# Arm_Board.net
KiCad netlist of a schematic drawn in EAGLE
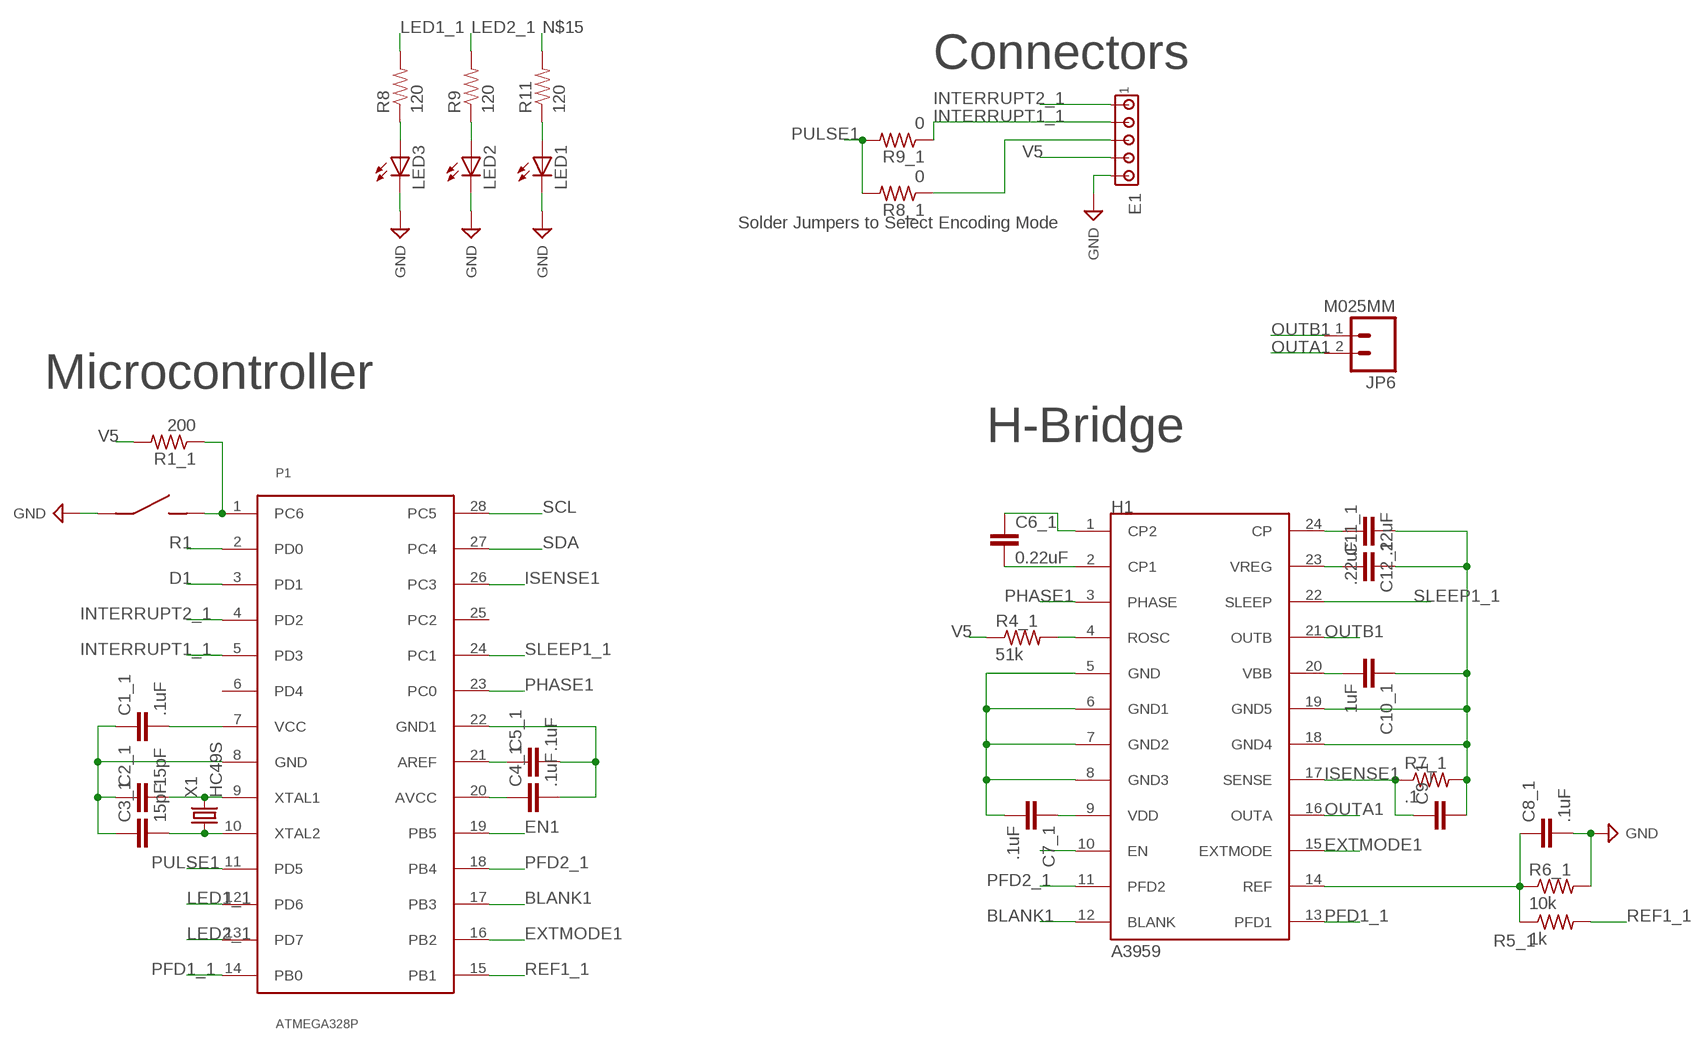
[diagram p0: schematic, sheet 1]
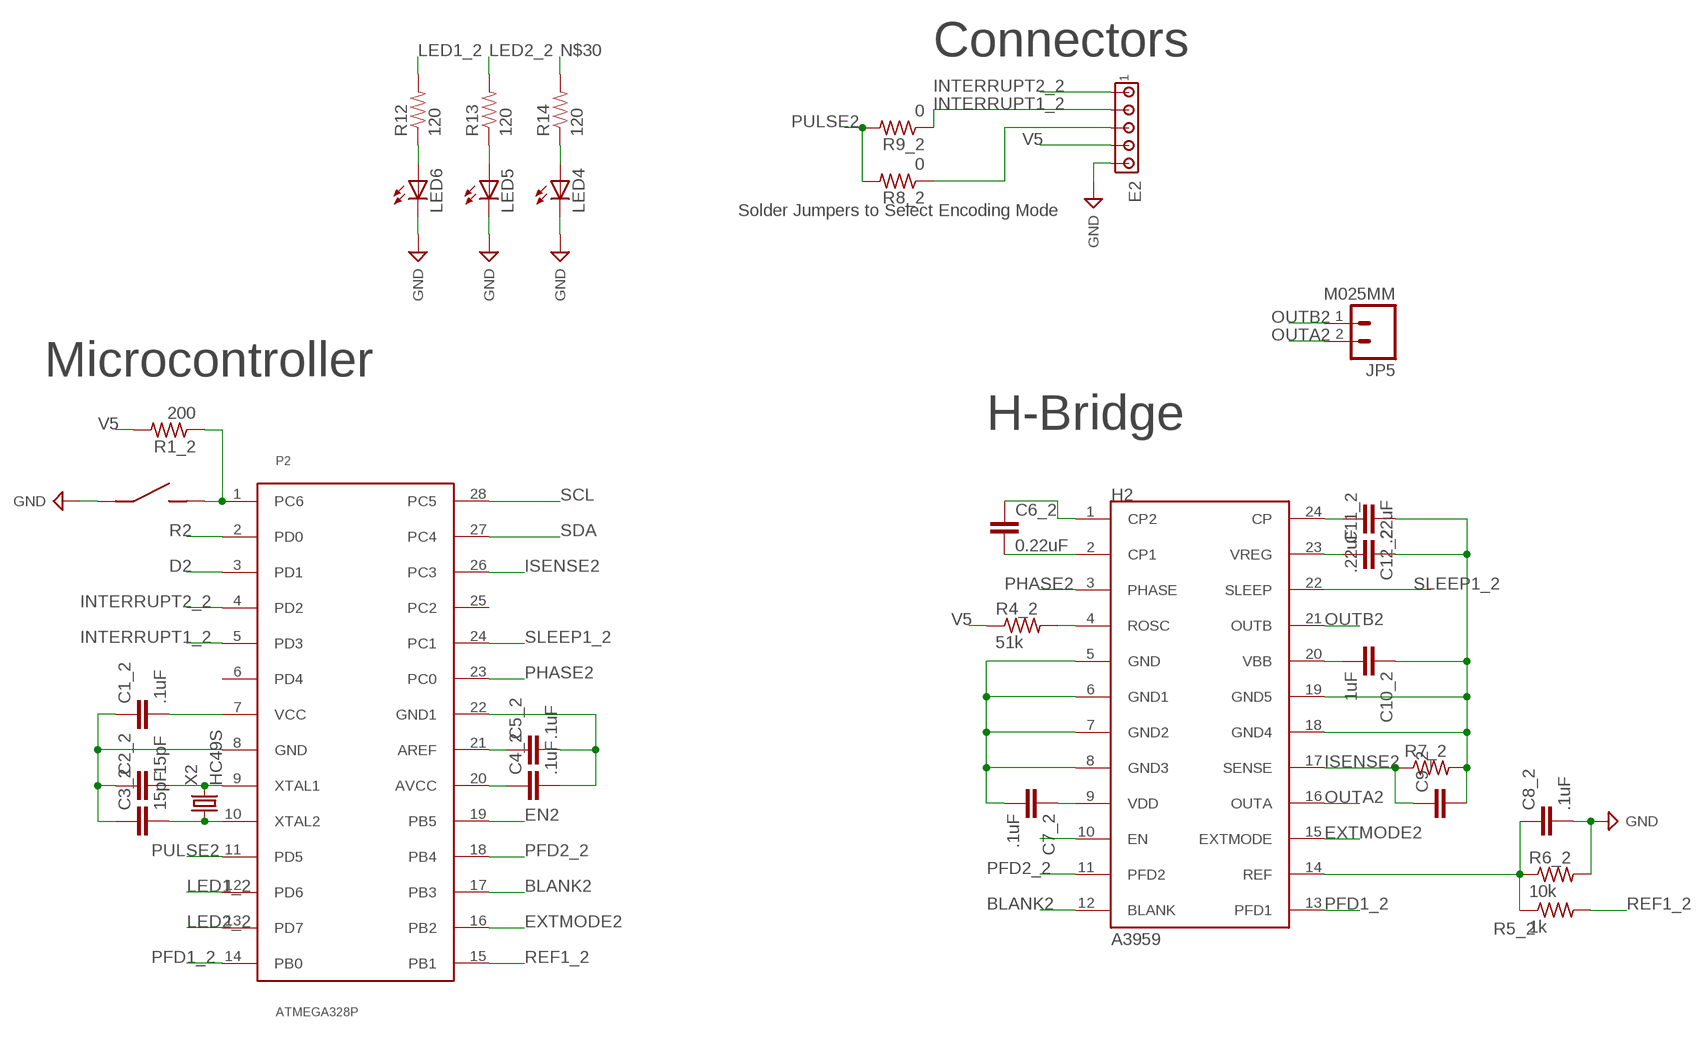
[diagram p1: schematic, sheet 2]
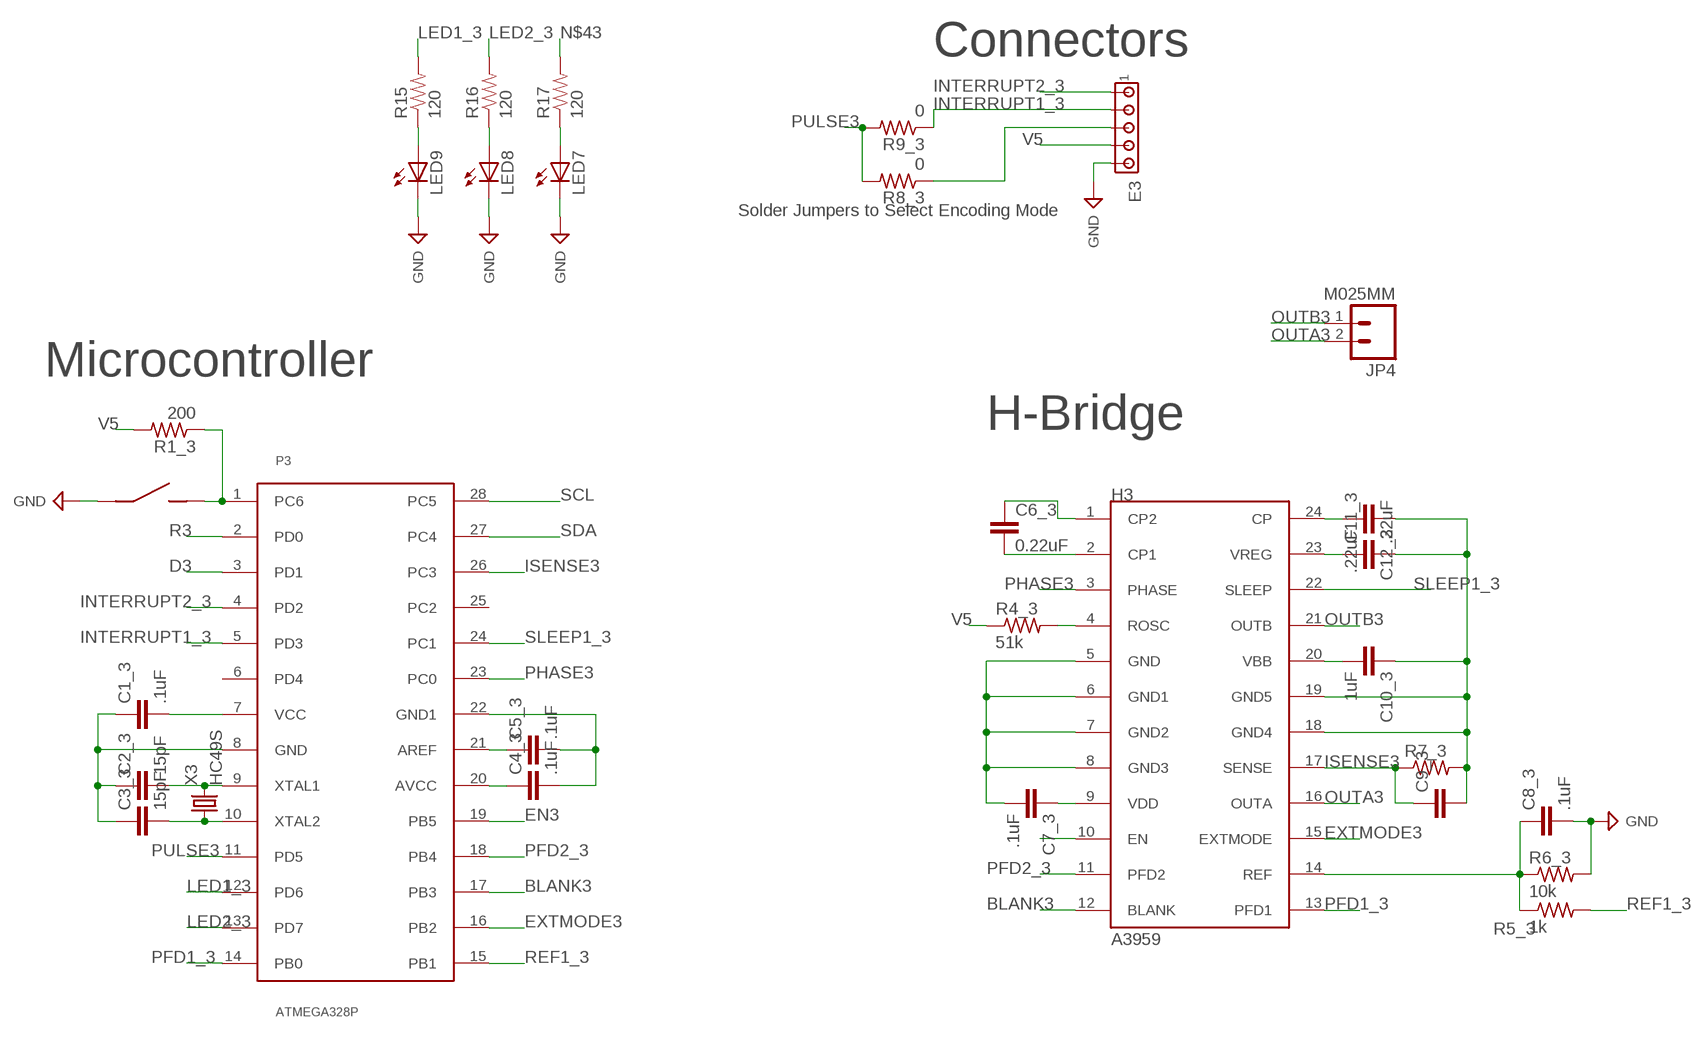
[diagram p2: schematic, sheet 3]
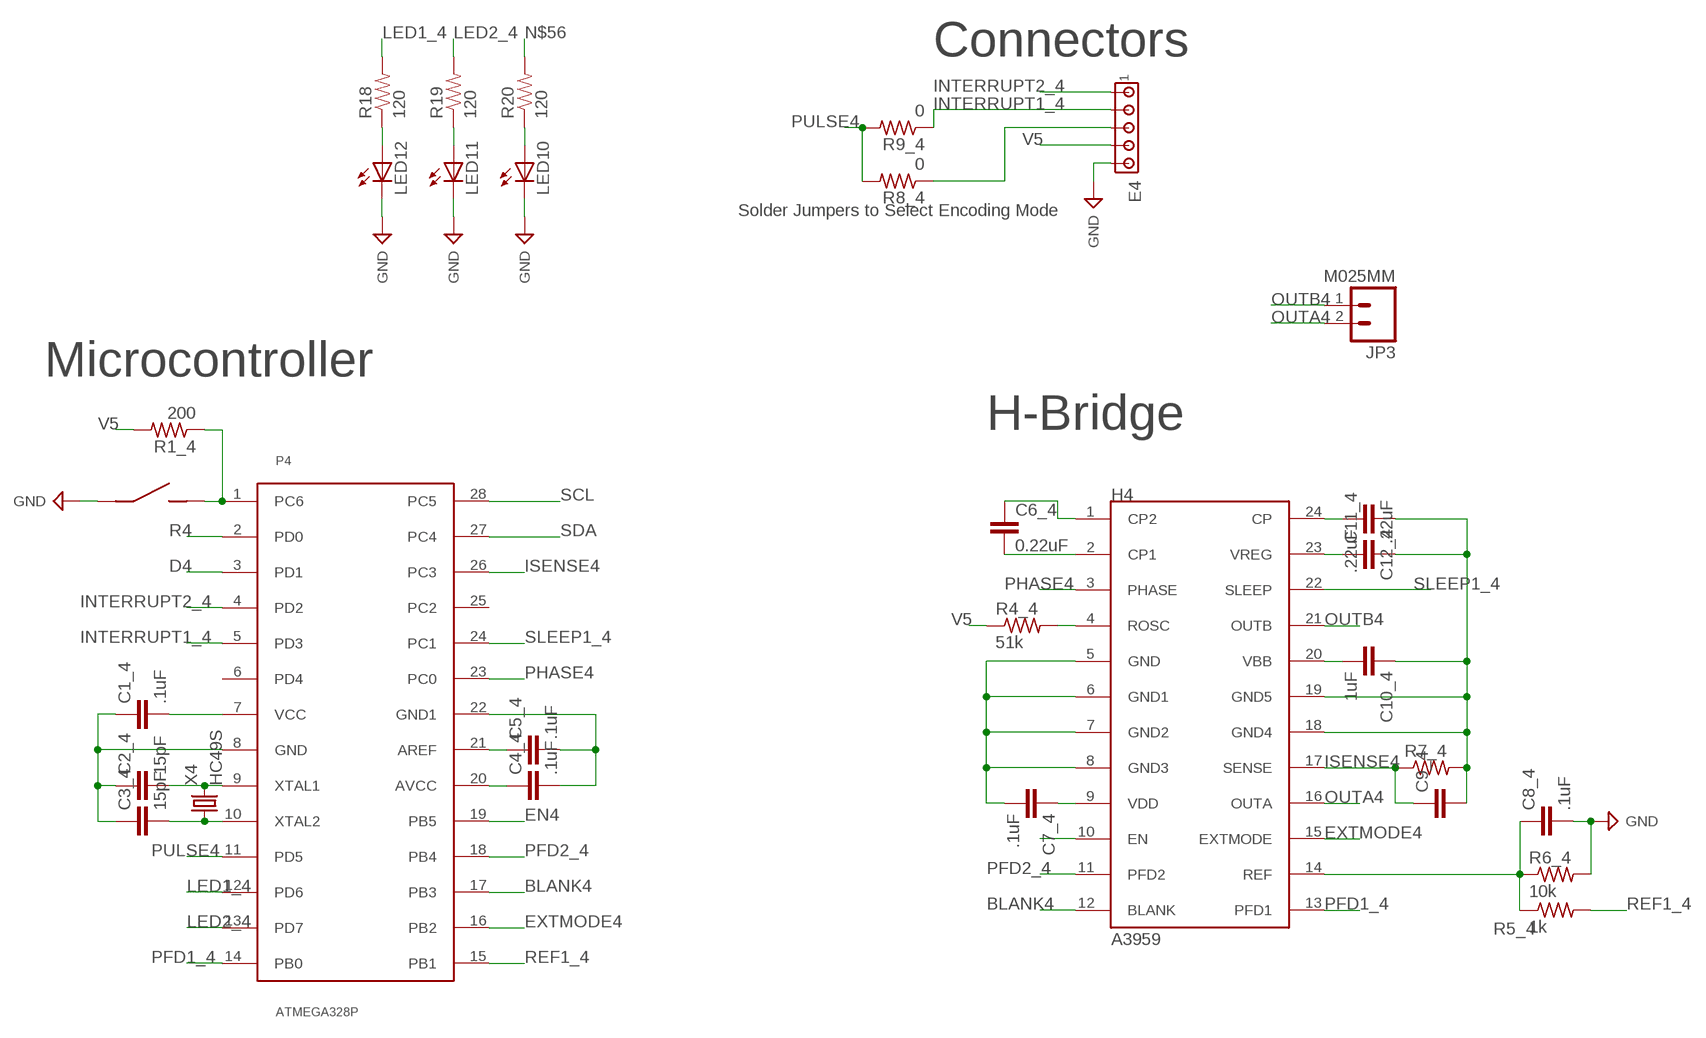
[diagram p3: schematic, sheet 4]
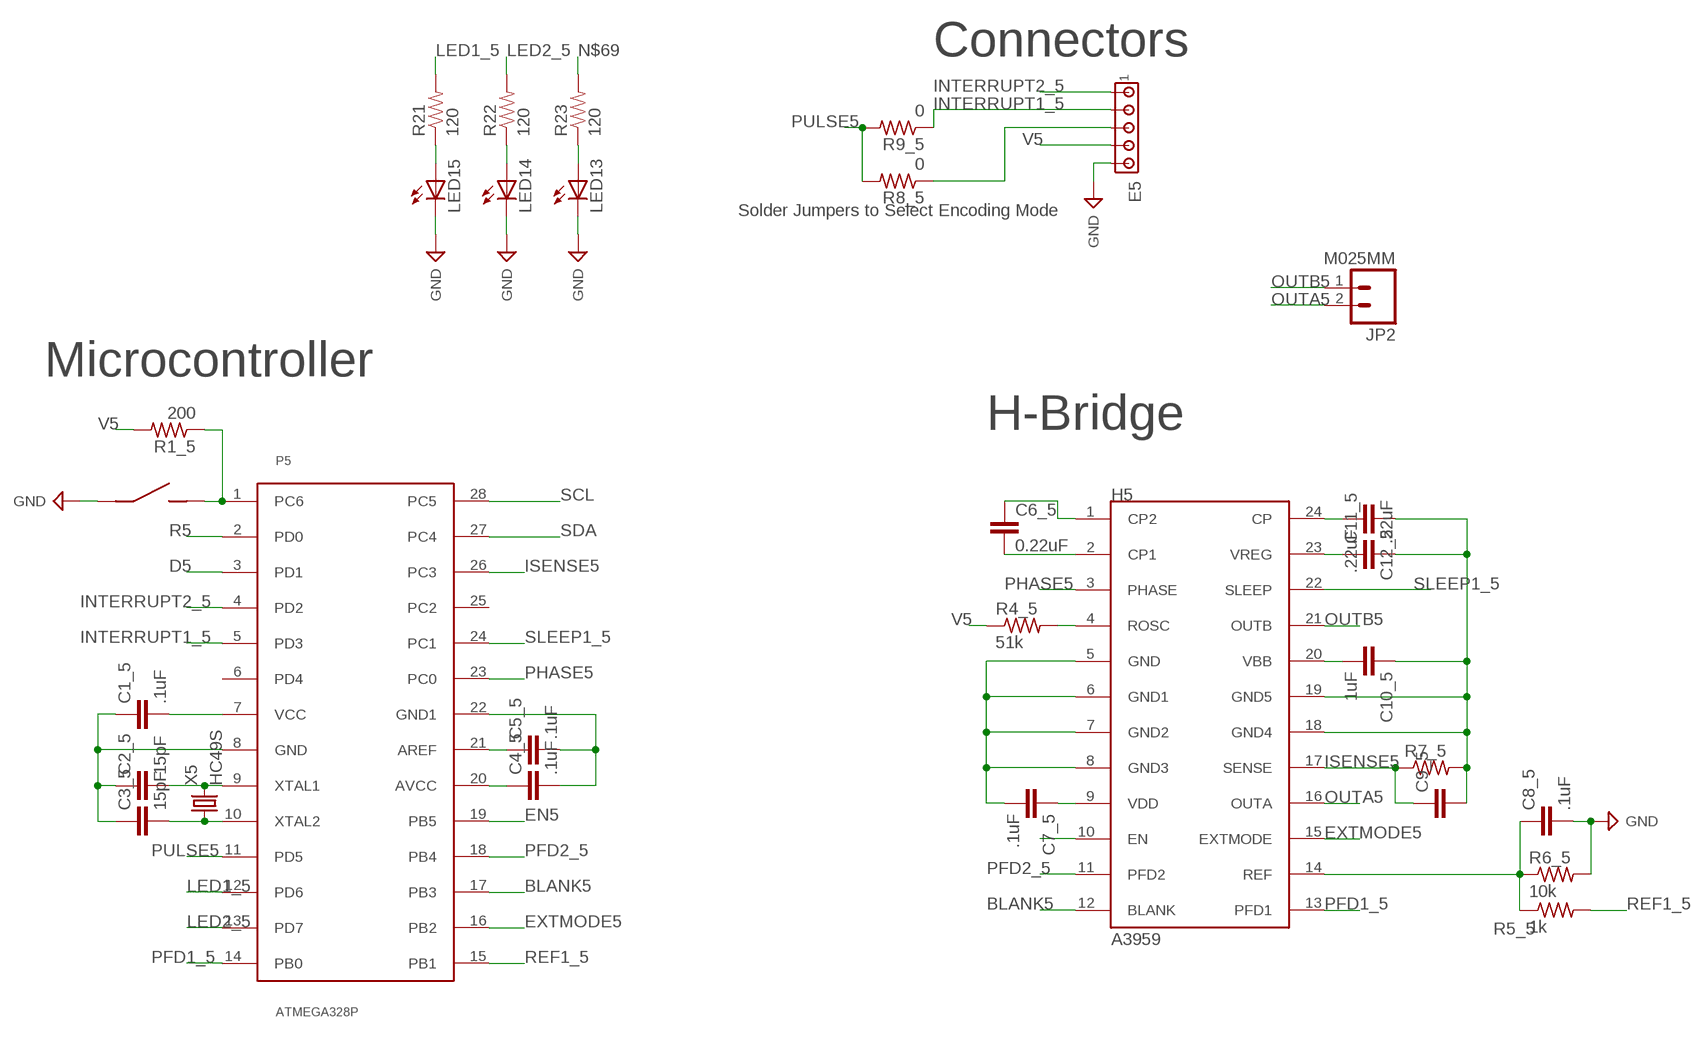
[diagram p4: schematic, sheet 5]
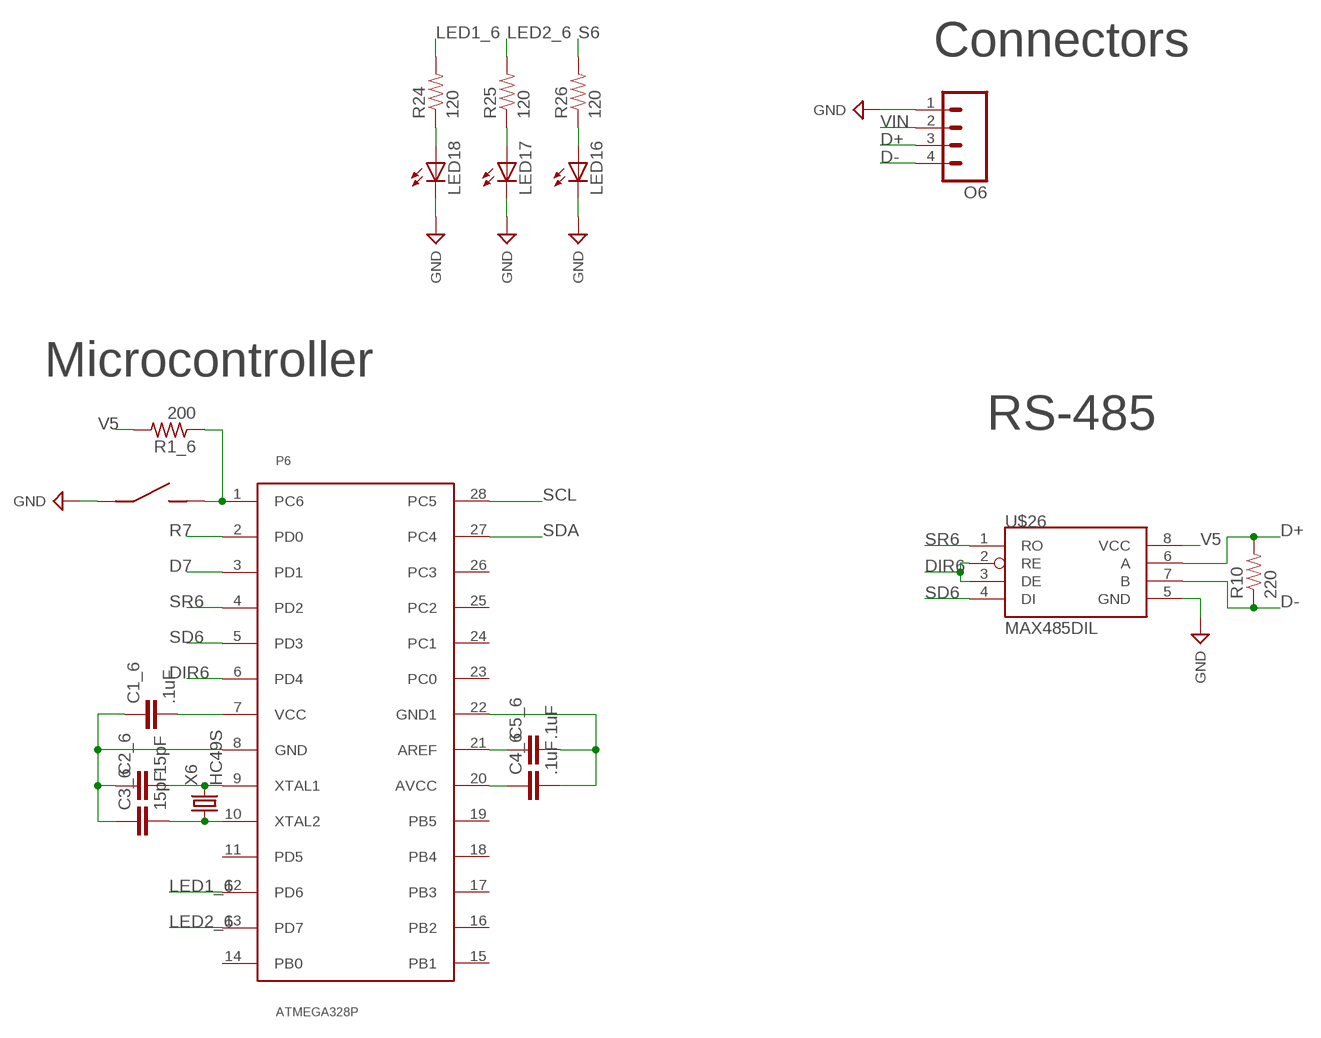
[diagram p5: schematic, sheet 6]
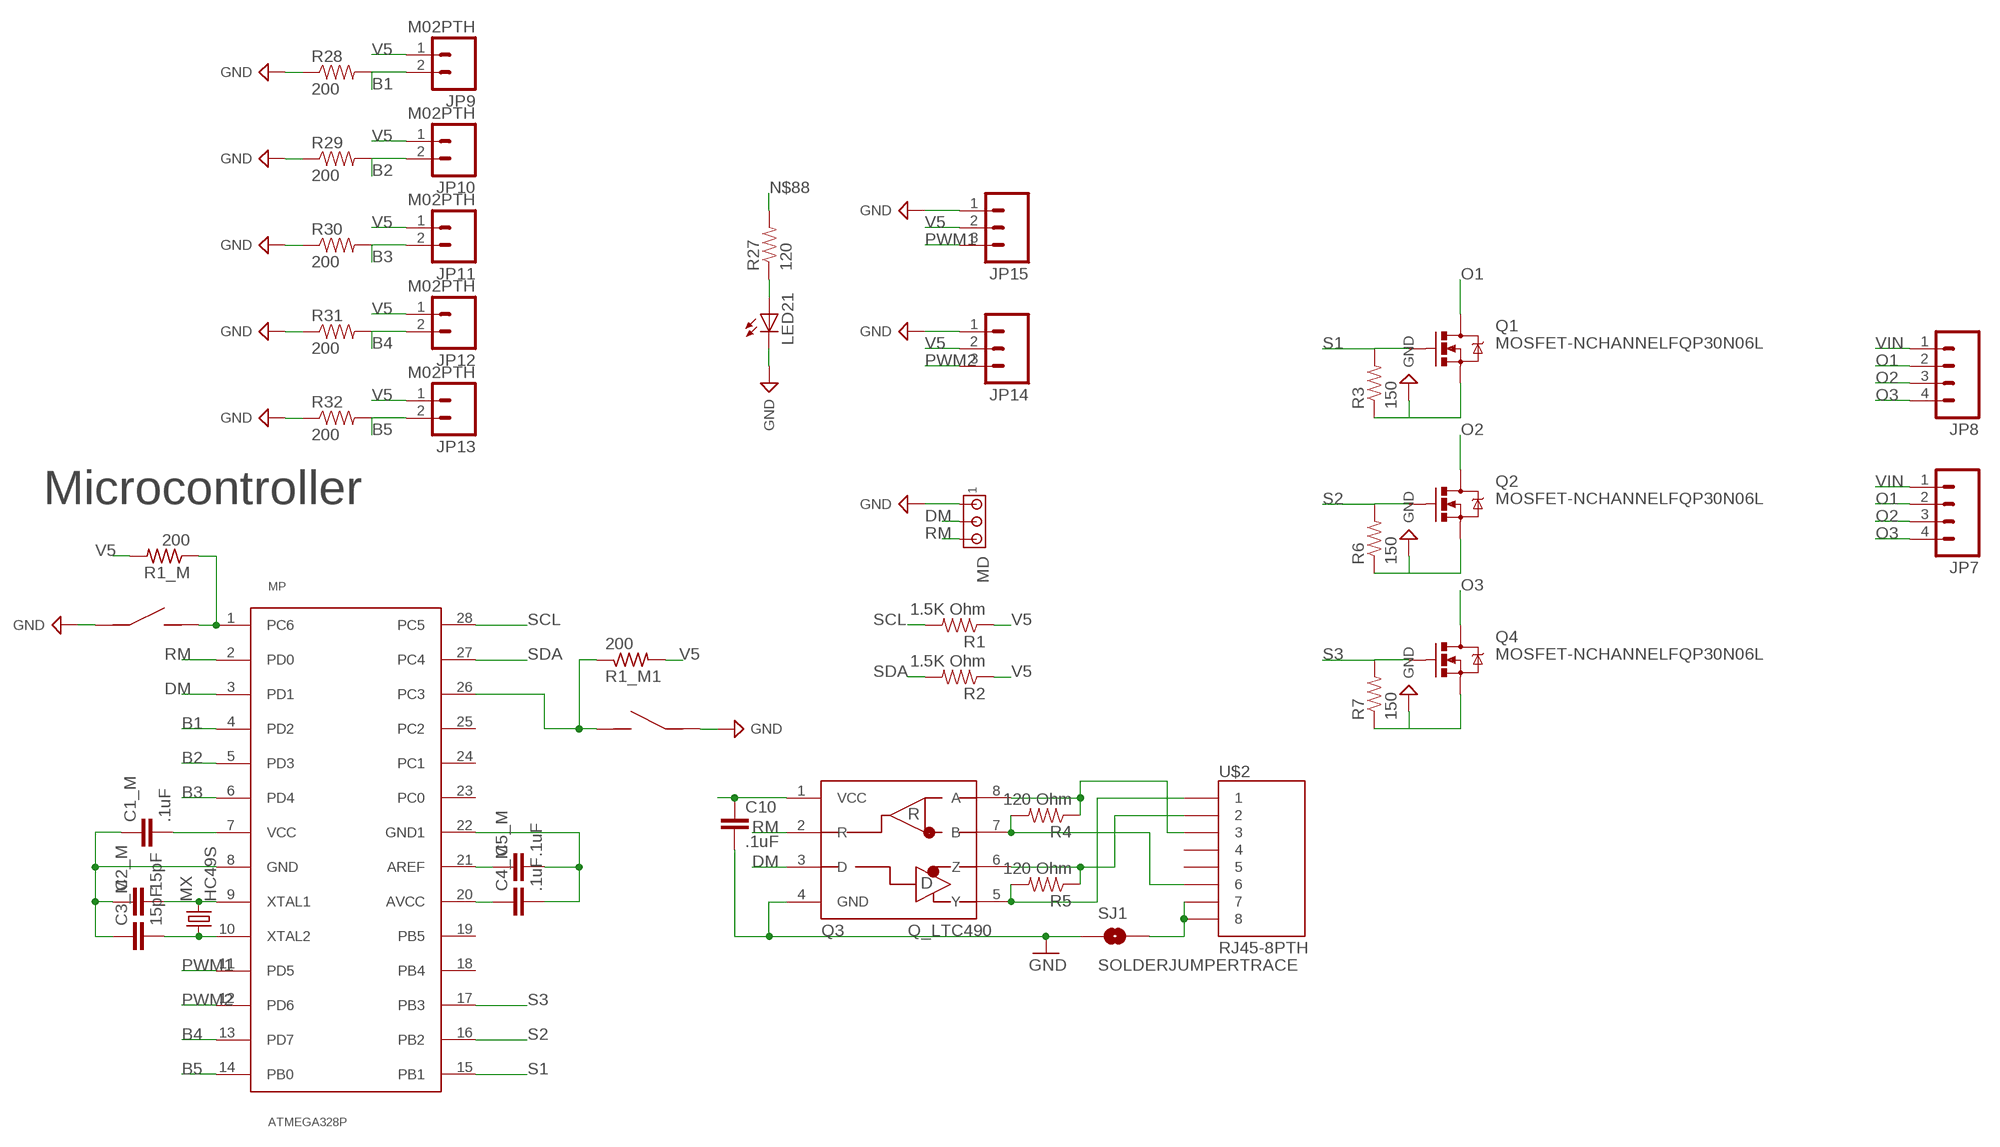
[diagram p6: schematic, sheet 7]
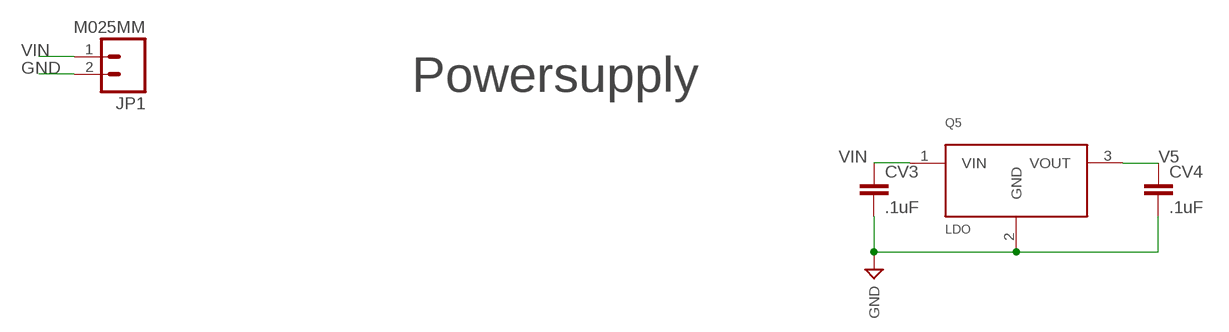
[diagram p7: schematic, sheet 8]

(export (version "E")
  (design (tool "Eeschema 10.0.6"))
  (components
    (comp (ref "CV3")
      (value ".1uF")
      (footprint "eagle-import:C_0805")
      (libsource (lib "eagle-import") (part "C_CAP_0805"))
    )
    (comp (ref "CV4")
      (value ".1uF")
      (footprint "eagle-import:C_0805")
      (libsource (lib "eagle-import") (part "C_CAP_0805"))
    )
    (comp (ref "JP1")
      (value "M025MM")
      (footprint "eagle-import:SCREWTERMINAL-5MM-2")
      (libsource (lib "eagle-import") (part "M025MM"))
    )
    (comp (ref "Q5")
      (value "LDO")
      (footprint "eagle-import:TO-220")
      (libsource (lib "eagle-import") (part "Q_LDO"))
    )
    (comp (ref "C1_6")
      (value ".1uF")
      (footprint "eagle-import:C_0805")
      (libsource (lib "eagle-import") (part "C_CAP_0805"))
    )
    (comp (ref "C2_6")
      (value "15pF")
      (footprint "eagle-import:C_0805")
      (libsource (lib "eagle-import") (part "C_CAP_0805"))
    )
    (comp (ref "C3_6")
      (value "15pF")
      (footprint "eagle-import:C_0805")
      (libsource (lib "eagle-import") (part "C_CAP_0805"))
    )
    (comp (ref "C4_6")
      (value ".1uF")
      (footprint "eagle-import:C_0805")
      (libsource (lib "eagle-import") (part "C_CAP_0805"))
    )
    (comp (ref "C5_6")
      (value ".1uF")
      (footprint "eagle-import:C_0805")
      (libsource (lib "eagle-import") (part "C_CAP_0805"))
    )
    (comp (ref "J6")
      (value "J_MC32857")
      (footprint "eagle-import:J_TOGGLE")
      (libsource (lib "eagle-import") (part "J_MC32857"))
    )
    (comp (ref "LED16")
      (value "LED1206")
      (footprint "eagle-import:LED-1206")
      (libsource (lib "eagle-import") (part "LED1206"))
    )
    (comp (ref "LED17")
      (value "LED1206")
      (footprint "eagle-import:LED-1206")
      (libsource (lib "eagle-import") (part "LED1206"))
    )
    (comp (ref "LED18")
      (value "LED1206")
      (footprint "eagle-import:LED-1206")
      (libsource (lib "eagle-import") (part "LED1206"))
    )
    (comp (ref "O6")
      (value "M041X04_NO_SILK")
      (footprint "eagle-import:1X04_NO_SILK")
      (libsource (lib "eagle-import") (part "M041X04_NO_SILK"))
    )
    (comp (ref "P6")
      (value "ATMEGA328P")
      (footprint "eagle-import:DIP28")
      (libsource (lib "eagle-import") (part "Q_ATMEGA328P"))
    )
    (comp (ref "R1_6")
      (value "200")
      (footprint "eagle-import:R_0805")
      (libsource (lib "eagle-import") (part "R_RES_0805"))
    )
    (comp (ref "R10")
      (value "220")
      (footprint "eagle-import:AXIAL-0.3EZ")
      (libsource (lib "eagle-import") (part "RESISTOREZ"))
    )
    (comp (ref "R24")
      (value "120")
      (footprint "eagle-import:1206")
      (libsource (lib "eagle-import") (part "RESISTOR1206"))
    )
    (comp (ref "R25")
      (value "120")
      (footprint "eagle-import:1206")
      (libsource (lib "eagle-import") (part "RESISTOR1206"))
    )
    (comp (ref "R26")
      (value "120")
      (footprint "eagle-import:1206")
      (libsource (lib "eagle-import") (part "RESISTOR1206"))
    )
    (comp (ref "U$26")
      (value "MAX485DIL")
      (footprint "eagle-import:DIL08")
      (libsource (lib "eagle-import") (part "MAX485DIL"))
    )
    (comp (ref "X6")
      (value "HC49S")
      (footprint "eagle-import:HC-49")
      (libsource (lib "eagle-import") (part "X_HC49SCRYSTAL"))
    )
    (comp (ref "C1_5")
      (value ".1uF")
      (footprint "eagle-import:C_0805")
      (libsource (lib "eagle-import") (part "C_CAP_0805"))
    )
    (comp (ref "C2_5")
      (value "15pF")
      (footprint "eagle-import:C_0805")
      (libsource (lib "eagle-import") (part "C_CAP_0805"))
    )
    (comp (ref "C3_5")
      (value "15pF")
      (footprint "eagle-import:C_0805")
      (libsource (lib "eagle-import") (part "C_CAP_0805"))
    )
    (comp (ref "C4_5")
      (value ".1uF")
      (footprint "eagle-import:C_0805")
      (libsource (lib "eagle-import") (part "C_CAP_0805"))
    )
    (comp (ref "C5_5")
      (value ".1uF")
      (footprint "eagle-import:C_0805")
      (libsource (lib "eagle-import") (part "C_CAP_0805"))
    )
    (comp (ref "C6_5")
      (value "0.22uF")
      (footprint "eagle-import:C_0805")
      (libsource (lib "eagle-import") (part "C_CAP_0805"))
    )
    (comp (ref "C7_5")
      (value ".1uF")
      (footprint "eagle-import:C_0805")
      (libsource (lib "eagle-import") (part "C_CAP_0805"))
    )
    (comp (ref "C8_5")
      (value ".1uF")
      (footprint "eagle-import:C_0805")
      (libsource (lib "eagle-import") (part "C_CAP_0805"))
    )
    (comp (ref "C9_5")
      (value "C_CAP_0805")
      (footprint "eagle-import:C_0805")
      (libsource (lib "eagle-import") (part "C_CAP_0805"))
    )
    (comp (ref "C10_5")
      (value "1uF")
      (footprint "eagle-import:C_0805")
      (libsource (lib "eagle-import") (part "C_CAP_0805"))
    )
    (comp (ref "C11_5")
      (value ".22uF")
      (footprint "eagle-import:C_0805")
      (libsource (lib "eagle-import") (part "C_CAP_0805"))
    )
    (comp (ref "C12_5")
      (value ".22uF")
      (footprint "eagle-import:C_0805")
      (libsource (lib "eagle-import") (part "C_CAP_0805"))
    )
    (comp (ref "E5")
      (value "J_MTA5P_100")
      (footprint "eagle-import:J_MTA100_5P")
      (libsource (lib "eagle-import") (part "J_MTA5P_100"))
    )
    (comp (ref "H5")
      (value "A3959")
      (footprint "eagle-import:DIP24")
      (libsource (lib "eagle-import") (part "Q_A3959"))
    )
    (comp (ref "JP2")
      (value "M025MM")
      (footprint "eagle-import:SCREWTERMINAL-5MM-2")
      (libsource (lib "eagle-import") (part "M025MM"))
    )
    (comp (ref "LED13")
      (value "LED1206")
      (footprint "eagle-import:LED-1206")
      (libsource (lib "eagle-import") (part "LED1206"))
    )
    (comp (ref "LED14")
      (value "LED1206")
      (footprint "eagle-import:LED-1206")
      (libsource (lib "eagle-import") (part "LED1206"))
    )
    (comp (ref "LED15")
      (value "LED1206")
      (footprint "eagle-import:LED-1206")
      (libsource (lib "eagle-import") (part "LED1206"))
    )
    (comp (ref "P5")
      (value "ATMEGA328P")
      (footprint "eagle-import:DIP28")
      (libsource (lib "eagle-import") (part "Q_ATMEGA328P"))
    )
    (comp (ref "R1_5")
      (value "200")
      (footprint "eagle-import:R_0805")
      (libsource (lib "eagle-import") (part "R_RES_0805"))
    )
    (comp (ref "R4_5")
      (value "51k")
      (footprint "eagle-import:R_0805")
      (libsource (lib "eagle-import") (part "R_RES_0805"))
    )
    (comp (ref "R5_5")
      (value "1k")
      (footprint "eagle-import:R_0805")
      (libsource (lib "eagle-import") (part "R_RES_0805"))
    )
    (comp (ref "R6_5")
      (value "10k")
      (footprint "eagle-import:R_0805")
      (libsource (lib "eagle-import") (part "R_RES_0805"))
    )
    (comp (ref "R7_5")
      (value "R_RES_2010")
      (footprint "eagle-import:R_2010")
      (libsource (lib "eagle-import") (part "R_RES_2010"))
    )
    (comp (ref "R8_5")
      (value "0")
      (footprint "eagle-import:R_0603")
      (libsource (lib "eagle-import") (part "R_RES_0603"))
    )
    (comp (ref "R9_5")
      (value "0")
      (footprint "eagle-import:R_0603")
      (libsource (lib "eagle-import") (part "R_RES_0603"))
    )
    (comp (ref "R21")
      (value "120")
      (footprint "eagle-import:1206")
      (libsource (lib "eagle-import") (part "RESISTOR1206"))
    )
    (comp (ref "R22")
      (value "120")
      (footprint "eagle-import:1206")
      (libsource (lib "eagle-import") (part "RESISTOR1206"))
    )
    (comp (ref "R23")
      (value "120")
      (footprint "eagle-import:1206")
      (libsource (lib "eagle-import") (part "RESISTOR1206"))
    )
    (comp (ref "S5")
      (value "J_MC32857")
      (footprint "eagle-import:J_TOGGLE")
      (libsource (lib "eagle-import") (part "J_MC32857"))
    )
    (comp (ref "X5")
      (value "HC49S")
      (footprint "eagle-import:HC-49")
      (libsource (lib "eagle-import") (part "X_HC49SCRYSTAL"))
    )
    (comp (ref "C1_M")
      (value ".1uF")
      (footprint "eagle-import:C_0805")
      (libsource (lib "eagle-import") (part "C_CAP_0805"))
    )
    (comp (ref "C2_M")
      (value "15pF")
      (footprint "eagle-import:C_0805")
      (libsource (lib "eagle-import") (part "C_CAP_0805"))
    )
    (comp (ref "C3_M")
      (value "15pF")
      (footprint "eagle-import:C_0805")
      (libsource (lib "eagle-import") (part "C_CAP_0805"))
    )
    (comp (ref "C4_M")
      (value ".1uF")
      (footprint "eagle-import:C_0805")
      (libsource (lib "eagle-import") (part "C_CAP_0805"))
    )
    (comp (ref "C5_M")
      (value ".1uF")
      (footprint "eagle-import:C_0805")
      (libsource (lib "eagle-import") (part "C_CAP_0805"))
    )
    (comp (ref "C10")
      (value ".1uF")
      (footprint "eagle-import:CAP-PTH-SMALL-KIT")
      (libsource (lib "eagle-import") (part "CAPKIT"))
    )
    (comp (ref "JP7")
      (value "M041X04_NO_SILK")
      (footprint "eagle-import:1X04_NO_SILK")
      (libsource (lib "eagle-import") (part "M041X04_NO_SILK"))
    )
    (comp (ref "JP8")
      (value "M041X04_NO_SILK")
      (footprint "eagle-import:1X04_NO_SILK")
      (libsource (lib "eagle-import") (part "M041X04_NO_SILK"))
    )
    (comp (ref "JP9")
      (value "M02PTH")
      (footprint "eagle-import:1X02")
      (libsource (lib "eagle-import") (part "M02PTH"))
    )
    (comp (ref "JP10")
      (value "M02PTH")
      (footprint "eagle-import:1X02")
      (libsource (lib "eagle-import") (part "M02PTH"))
    )
    (comp (ref "JP11")
      (value "M02PTH")
      (footprint "eagle-import:1X02")
      (libsource (lib "eagle-import") (part "M02PTH"))
    )
    (comp (ref "JP12")
      (value "M02PTH")
      (footprint "eagle-import:1X02")
      (libsource (lib "eagle-import") (part "M02PTH"))
    )
    (comp (ref "JP13")
      (value "M02PTH")
      (footprint "eagle-import:1X02")
      (libsource (lib "eagle-import") (part "M02PTH"))
    )
    (comp (ref "JP14")
      (value "M03PTH")
      (footprint "eagle-import:1X03")
      (libsource (lib "eagle-import") (part "M03PTH"))
    )
    (comp (ref "JP15")
      (value "M03PTH")
      (footprint "eagle-import:1X03")
      (libsource (lib "eagle-import") (part "M03PTH"))
    )
    (comp (ref "LED21")
      (value "LED1206")
      (footprint "eagle-import:LED-1206")
      (libsource (lib "eagle-import") (part "LED1206"))
    )
    (comp (ref "MD")
      (value "J_MTA3P_100")
      (footprint "eagle-import:J_MTA100_3P")
      (libsource (lib "eagle-import") (part "J_MTA3P_100"))
    )
    (comp (ref "MP")
      (value "ATMEGA328P")
      (footprint "eagle-import:DIP28")
      (libsource (lib "eagle-import") (part "Q_ATMEGA328P"))
    )
    (comp (ref "MS")
      (value "J_MC32857")
      (footprint "eagle-import:J_TOGGLE")
      (libsource (lib "eagle-import") (part "J_MC32857"))
    )
    (comp (ref "MS1")
      (value "J_MC32857")
      (footprint "eagle-import:J_TOGGLE")
      (libsource (lib "eagle-import") (part "J_MC32857"))
    )
    (comp (ref "MX")
      (value "HC49S")
      (footprint "eagle-import:HC-49")
      (libsource (lib "eagle-import") (part "X_HC49SCRYSTAL"))
    )
    (comp (ref "Q1")
      (value "MOSFET-NCHANNELFQP30N06L")
      (footprint "eagle-import:TO220V")
      (libsource (lib "eagle-import") (part "MOSFET-NCHANNELFQP30N06L"))
    )
    (comp (ref "Q2")
      (value "MOSFET-NCHANNELFQP30N06L")
      (footprint "eagle-import:TO220V")
      (libsource (lib "eagle-import") (part "MOSFET-NCHANNELFQP30N06L"))
    )
    (comp (ref "Q3")
      (value "Q_LTC490")
      (footprint "eagle-import:DIP8")
      (libsource (lib "eagle-import") (part "Q_LTC490"))
    )
    (comp (ref "Q4")
      (value "MOSFET-NCHANNELFQP30N06L")
      (footprint "eagle-import:TO220V")
      (libsource (lib "eagle-import") (part "MOSFET-NCHANNELFQP30N06L"))
    )
    (comp (ref "R1")
      (value "1.5K Ohm")
      (footprint "eagle-import:AXIAL-0.3")
      (libsource (lib "eagle-import") (part "RESISTORAXIAL-0.3"))
    )
    (comp (ref "R1_M")
      (value "200")
      (footprint "eagle-import:R_0805")
      (libsource (lib "eagle-import") (part "R_RES_0805"))
    )
    (comp (ref "R1_M1")
      (value "200")
      (footprint "eagle-import:R_0805")
      (libsource (lib "eagle-import") (part "R_RES_0805"))
    )
    (comp (ref "R2")
      (value "1.5K Ohm")
      (footprint "eagle-import:AXIAL-0.3")
      (libsource (lib "eagle-import") (part "RESISTORAXIAL-0.3"))
    )
    (comp (ref "R3")
      (value "150")
      (footprint "eagle-import:AXIAL-0.3-KIT")
      (libsource (lib "eagle-import") (part "10KOHM1/6W5%(PTH)KIT"))
    )
    (comp (ref "R4")
      (value "120 Ohm")
      (footprint "eagle-import:AXIAL-0.3")
      (libsource (lib "eagle-import") (part "RESISTORAXIAL-0.3"))
    )
    (comp (ref "R5")
      (value "120 Ohm")
      (footprint "eagle-import:AXIAL-0.3")
      (libsource (lib "eagle-import") (part "RESISTORAXIAL-0.3"))
    )
    (comp (ref "R6")
      (value "150")
      (footprint "eagle-import:AXIAL-0.3-KIT")
      (libsource (lib "eagle-import") (part "10KOHM1/6W5%(PTH)KIT"))
    )
    (comp (ref "R7")
      (value "150")
      (footprint "eagle-import:AXIAL-0.3-KIT")
      (libsource (lib "eagle-import") (part "10KOHM1/6W5%(PTH)KIT"))
    )
    (comp (ref "R27")
      (value "120")
      (footprint "eagle-import:1206")
      (libsource (lib "eagle-import") (part "RESISTOR1206"))
    )
    (comp (ref "R28")
      (value "200")
      (footprint "eagle-import:1_6W-RES")
      (libsource (lib "eagle-import") (part "RESISTORPTH-1/6W"))
    )
    (comp (ref "R29")
      (value "200")
      (footprint "eagle-import:1_6W-RES")
      (libsource (lib "eagle-import") (part "RESISTORPTH-1/6W"))
    )
    (comp (ref "R30")
      (value "200")
      (footprint "eagle-import:1_6W-RES")
      (libsource (lib "eagle-import") (part "RESISTORPTH-1/6W"))
    )
    (comp (ref "R31")
      (value "200")
      (footprint "eagle-import:1_6W-RES")
      (libsource (lib "eagle-import") (part "RESISTORPTH-1/6W"))
    )
    (comp (ref "R32")
      (value "200")
      (footprint "eagle-import:1_6W-RES")
      (libsource (lib "eagle-import") (part "RESISTORPTH-1/6W"))
    )
    (comp (ref "SJ1")
      (value "SOLDERJUMPERTRACE")
      (footprint "eagle-import:SJ_2S-TRACE")
      (libsource (lib "eagle-import") (part "SOLDERJUMPERTRACE"))
    )
    (comp (ref "U$2")
      (value "RJ45-8PTH")
      (footprint "eagle-import:RJ45-8")
      (libsource (lib "eagle-import") (part "RJ45-8PTH"))
    )
    (comp (ref "C1_3")
      (value ".1uF")
      (footprint "eagle-import:C_0805")
      (libsource (lib "eagle-import") (part "C_CAP_0805"))
    )
    (comp (ref "C2_3")
      (value "15pF")
      (footprint "eagle-import:C_0805")
      (libsource (lib "eagle-import") (part "C_CAP_0805"))
    )
    (comp (ref "C3_3")
      (value "15pF")
      (footprint "eagle-import:C_0805")
      (libsource (lib "eagle-import") (part "C_CAP_0805"))
    )
    (comp (ref "C4_3")
      (value ".1uF")
      (footprint "eagle-import:C_0805")
      (libsource (lib "eagle-import") (part "C_CAP_0805"))
    )
    (comp (ref "C5_3")
      (value ".1uF")
      (footprint "eagle-import:C_0805")
      (libsource (lib "eagle-import") (part "C_CAP_0805"))
    )
    (comp (ref "C6_3")
      (value "0.22uF")
      (footprint "eagle-import:C_0805")
      (libsource (lib "eagle-import") (part "C_CAP_0805"))
    )
    (comp (ref "C7_3")
      (value ".1uF")
      (footprint "eagle-import:C_0805")
      (libsource (lib "eagle-import") (part "C_CAP_0805"))
    )
    (comp (ref "C8_3")
      (value ".1uF")
      (footprint "eagle-import:C_0805")
      (libsource (lib "eagle-import") (part "C_CAP_0805"))
    )
    (comp (ref "C9_3")
      (value "C_CAP_0805")
      (footprint "eagle-import:C_0805")
      (libsource (lib "eagle-import") (part "C_CAP_0805"))
    )
    (comp (ref "C10_3")
      (value "1uF")
      (footprint "eagle-import:C_0805")
      (libsource (lib "eagle-import") (part "C_CAP_0805"))
    )
    (comp (ref "C11_3")
      (value ".22uF")
      (footprint "eagle-import:C_0805")
      (libsource (lib "eagle-import") (part "C_CAP_0805"))
    )
    (comp (ref "C12_3")
      (value ".22uF")
      (footprint "eagle-import:C_0805")
      (libsource (lib "eagle-import") (part "C_CAP_0805"))
    )
    (comp (ref "E3")
      (value "J_MTA5P_100")
      (footprint "eagle-import:J_MTA100_5P")
      (libsource (lib "eagle-import") (part "J_MTA5P_100"))
    )
    (comp (ref "H3")
      (value "A3959")
      (footprint "eagle-import:DIP24")
      (libsource (lib "eagle-import") (part "Q_A3959"))
    )
    (comp (ref "JP4")
      (value "M025MM")
      (footprint "eagle-import:SCREWTERMINAL-5MM-2")
      (libsource (lib "eagle-import") (part "M025MM"))
    )
    (comp (ref "LED7")
      (value "LED1206")
      (footprint "eagle-import:LED-1206")
      (libsource (lib "eagle-import") (part "LED1206"))
    )
    (comp (ref "LED8")
      (value "LED1206")
      (footprint "eagle-import:LED-1206")
      (libsource (lib "eagle-import") (part "LED1206"))
    )
    (comp (ref "LED9")
      (value "LED1206")
      (footprint "eagle-import:LED-1206")
      (libsource (lib "eagle-import") (part "LED1206"))
    )
    (comp (ref "P3")
      (value "ATMEGA328P")
      (footprint "eagle-import:DIP28")
      (libsource (lib "eagle-import") (part "Q_ATMEGA328P"))
    )
    (comp (ref "R1_3")
      (value "200")
      (footprint "eagle-import:R_0805")
      (libsource (lib "eagle-import") (part "R_RES_0805"))
    )
    (comp (ref "R4_3")
      (value "51k")
      (footprint "eagle-import:R_0805")
      (libsource (lib "eagle-import") (part "R_RES_0805"))
    )
    (comp (ref "R5_3")
      (value "1k")
      (footprint "eagle-import:R_0805")
      (libsource (lib "eagle-import") (part "R_RES_0805"))
    )
    (comp (ref "R6_3")
      (value "10k")
      (footprint "eagle-import:R_0805")
      (libsource (lib "eagle-import") (part "R_RES_0805"))
    )
    (comp (ref "R7_3")
      (value "R_RES_2010")
      (footprint "eagle-import:R_2010")
      (libsource (lib "eagle-import") (part "R_RES_2010"))
    )
    (comp (ref "R8_3")
      (value "0")
      (footprint "eagle-import:R_0603")
      (libsource (lib "eagle-import") (part "R_RES_0603"))
    )
    (comp (ref "R9_3")
      (value "0")
      (footprint "eagle-import:R_0603")
      (libsource (lib "eagle-import") (part "R_RES_0603"))
    )
    (comp (ref "R15")
      (value "120")
      (footprint "eagle-import:1206")
      (libsource (lib "eagle-import") (part "RESISTOR1206"))
    )
    (comp (ref "R16")
      (value "120")
      (footprint "eagle-import:1206")
      (libsource (lib "eagle-import") (part "RESISTOR1206"))
    )
    (comp (ref "R17")
      (value "120")
      (footprint "eagle-import:1206")
      (libsource (lib "eagle-import") (part "RESISTOR1206"))
    )
    (comp (ref "S3")
      (value "J_MC32857")
      (footprint "eagle-import:J_TOGGLE")
      (libsource (lib "eagle-import") (part "J_MC32857"))
    )
    (comp (ref "X3")
      (value "HC49S")
      (footprint "eagle-import:HC-49")
      (libsource (lib "eagle-import") (part "X_HC49SCRYSTAL"))
    )
    (comp (ref "C1_1")
      (value ".1uF")
      (footprint "eagle-import:C_0805")
      (libsource (lib "eagle-import") (part "C_CAP_0805"))
    )
    (comp (ref "C2_1")
      (value "15pF")
      (footprint "eagle-import:C_0805")
      (libsource (lib "eagle-import") (part "C_CAP_0805"))
    )
    (comp (ref "C3_1")
      (value "15pF")
      (footprint "eagle-import:C_0805")
      (libsource (lib "eagle-import") (part "C_CAP_0805"))
    )
    (comp (ref "C4_1")
      (value ".1uF")
      (footprint "eagle-import:C_0805")
      (libsource (lib "eagle-import") (part "C_CAP_0805"))
    )
    (comp (ref "C5_1")
      (value ".1uF")
      (footprint "eagle-import:C_0805")
      (libsource (lib "eagle-import") (part "C_CAP_0805"))
    )
    (comp (ref "C6_1")
      (value "0.22uF")
      (footprint "eagle-import:C_0805")
      (libsource (lib "eagle-import") (part "C_CAP_0805"))
    )
    (comp (ref "C7_1")
      (value ".1uF")
      (footprint "eagle-import:C_0805")
      (libsource (lib "eagle-import") (part "C_CAP_0805"))
    )
    (comp (ref "C8_1")
      (value ".1uF")
      (footprint "eagle-import:C_0805")
      (libsource (lib "eagle-import") (part "C_CAP_0805"))
    )
    (comp (ref "C9_1")
      (value "C_CAP_0805")
      (footprint "eagle-import:C_0805")
      (libsource (lib "eagle-import") (part "C_CAP_0805"))
    )
    (comp (ref "C10_1")
      (value "1uF")
      (footprint "eagle-import:C_0805")
      (libsource (lib "eagle-import") (part "C_CAP_0805"))
    )
    (comp (ref "C11_1")
      (value ".22uF")
      (footprint "eagle-import:C_0805")
      (libsource (lib "eagle-import") (part "C_CAP_0805"))
    )
    (comp (ref "C12_1")
      (value ".22uF")
      (footprint "eagle-import:C_0805")
      (libsource (lib "eagle-import") (part "C_CAP_0805"))
    )
    (comp (ref "E1")
      (value "J_MTA5P_100")
      (footprint "eagle-import:J_MTA100_5P")
      (libsource (lib "eagle-import") (part "J_MTA5P_100"))
    )
    (comp (ref "H1")
      (value "A3959")
      (footprint "eagle-import:DIP24")
      (libsource (lib "eagle-import") (part "Q_A3959"))
    )
    (comp (ref "JP6")
      (value "M025MM")
      (footprint "eagle-import:SCREWTERMINAL-5MM-2")
      (libsource (lib "eagle-import") (part "M025MM"))
    )
    (comp (ref "LED1")
      (value "LED1206")
      (footprint "eagle-import:LED-1206")
      (libsource (lib "eagle-import") (part "LED1206"))
    )
    (comp (ref "LED2")
      (value "LED1206")
      (footprint "eagle-import:LED-1206")
      (libsource (lib "eagle-import") (part "LED1206"))
    )
    (comp (ref "LED3")
      (value "LED1206")
      (footprint "eagle-import:LED-1206")
      (libsource (lib "eagle-import") (part "LED1206"))
    )
    (comp (ref "P1")
      (value "ATMEGA328P")
      (footprint "eagle-import:DIP28")
      (libsource (lib "eagle-import") (part "Q_ATMEGA328P"))
    )
    (comp (ref "R1_1")
      (value "200")
      (footprint "eagle-import:R_0805")
      (libsource (lib "eagle-import") (part "R_RES_0805"))
    )
    (comp (ref "R4_1")
      (value "51k")
      (footprint "eagle-import:R_0805")
      (libsource (lib "eagle-import") (part "R_RES_0805"))
    )
    (comp (ref "R5_1")
      (value "1k")
      (footprint "eagle-import:R_0805")
      (libsource (lib "eagle-import") (part "R_RES_0805"))
    )
    (comp (ref "R6_1")
      (value "10k")
      (footprint "eagle-import:R_0805")
      (libsource (lib "eagle-import") (part "R_RES_0805"))
    )
    (comp (ref "R7_1")
      (value ".1")
      (footprint "eagle-import:R_2010")
      (libsource (lib "eagle-import") (part "R_RES_2010"))
    )
    (comp (ref "R8")
      (value "120")
      (footprint "eagle-import:1206")
      (libsource (lib "eagle-import") (part "RESISTOR1206"))
    )
    (comp (ref "R8_1")
      (value "0")
      (footprint "eagle-import:R_0603")
      (libsource (lib "eagle-import") (part "R_RES_0603"))
    )
    (comp (ref "R9")
      (value "120")
      (footprint "eagle-import:1206")
      (libsource (lib "eagle-import") (part "RESISTOR1206"))
    )
    (comp (ref "R9_1")
      (value "0")
      (footprint "eagle-import:R_0603")
      (libsource (lib "eagle-import") (part "R_RES_0603"))
    )
    (comp (ref "R11")
      (value "120")
      (footprint "eagle-import:1206")
      (libsource (lib "eagle-import") (part "RESISTOR1206"))
    )
    (comp (ref "S1")
      (value "J_MC32857")
      (footprint "eagle-import:J_TOGGLE")
      (libsource (lib "eagle-import") (part "J_MC32857"))
    )
    (comp (ref "X1")
      (value "HC49S")
      (footprint "eagle-import:HC-49")
      (libsource (lib "eagle-import") (part "X_HC49SCRYSTAL"))
    )
    (comp (ref "C1_4")
      (value ".1uF")
      (footprint "eagle-import:C_0805")
      (libsource (lib "eagle-import") (part "C_CAP_0805"))
    )
    (comp (ref "C2_4")
      (value "15pF")
      (footprint "eagle-import:C_0805")
      (libsource (lib "eagle-import") (part "C_CAP_0805"))
    )
    (comp (ref "C3_4")
      (value "15pF")
      (footprint "eagle-import:C_0805")
      (libsource (lib "eagle-import") (part "C_CAP_0805"))
    )
    (comp (ref "C4_4")
      (value ".1uF")
      (footprint "eagle-import:C_0805")
      (libsource (lib "eagle-import") (part "C_CAP_0805"))
    )
    (comp (ref "C5_4")
      (value ".1uF")
      (footprint "eagle-import:C_0805")
      (libsource (lib "eagle-import") (part "C_CAP_0805"))
    )
    (comp (ref "C6_4")
      (value "0.22uF")
      (footprint "eagle-import:C_0805")
      (libsource (lib "eagle-import") (part "C_CAP_0805"))
    )
    (comp (ref "C7_4")
      (value ".1uF")
      (footprint "eagle-import:C_0805")
      (libsource (lib "eagle-import") (part "C_CAP_0805"))
    )
    (comp (ref "C8_4")
      (value ".1uF")
      (footprint "eagle-import:C_0805")
      (libsource (lib "eagle-import") (part "C_CAP_0805"))
    )
    (comp (ref "C9_4")
      (value "C_CAP_0805")
      (footprint "eagle-import:C_0805")
      (libsource (lib "eagle-import") (part "C_CAP_0805"))
    )
    (comp (ref "C10_4")
      (value "1uF")
      (footprint "eagle-import:C_0805")
      (libsource (lib "eagle-import") (part "C_CAP_0805"))
    )
    (comp (ref "C11_4")
      (value ".22uF")
      (footprint "eagle-import:C_0805")
      (libsource (lib "eagle-import") (part "C_CAP_0805"))
    )
    (comp (ref "C12_4")
      (value ".22uF")
      (footprint "eagle-import:C_0805")
      (libsource (lib "eagle-import") (part "C_CAP_0805"))
    )
    (comp (ref "E4")
      (value "J_MTA5P_100")
      (footprint "eagle-import:J_MTA100_5P")
      (libsource (lib "eagle-import") (part "J_MTA5P_100"))
    )
    (comp (ref "H4")
      (value "A3959")
      (footprint "eagle-import:DIP24")
      (libsource (lib "eagle-import") (part "Q_A3959"))
    )
    (comp (ref "JP3")
      (value "M025MM")
      (footprint "eagle-import:SCREWTERMINAL-5MM-2")
      (libsource (lib "eagle-import") (part "M025MM"))
    )
    (comp (ref "LED10")
      (value "LED1206")
      (footprint "eagle-import:LED-1206")
      (libsource (lib "eagle-import") (part "LED1206"))
    )
    (comp (ref "LED11")
      (value "LED1206")
      (footprint "eagle-import:LED-1206")
      (libsource (lib "eagle-import") (part "LED1206"))
    )
    (comp (ref "LED12")
      (value "LED1206")
      (footprint "eagle-import:LED-1206")
      (libsource (lib "eagle-import") (part "LED1206"))
    )
    (comp (ref "P4")
      (value "ATMEGA328P")
      (footprint "eagle-import:DIP28")
      (libsource (lib "eagle-import") (part "Q_ATMEGA328P"))
    )
    (comp (ref "R1_4")
      (value "200")
      (footprint "eagle-import:R_0805")
      (libsource (lib "eagle-import") (part "R_RES_0805"))
    )
    (comp (ref "R4_4")
      (value "51k")
      (footprint "eagle-import:R_0805")
      (libsource (lib "eagle-import") (part "R_RES_0805"))
    )
    (comp (ref "R5_4")
      (value "1k")
      (footprint "eagle-import:R_0805")
      (libsource (lib "eagle-import") (part "R_RES_0805"))
    )
    (comp (ref "R6_4")
      (value "10k")
      (footprint "eagle-import:R_0805")
      (libsource (lib "eagle-import") (part "R_RES_0805"))
    )
    (comp (ref "R7_4")
      (value "R_RES_2010")
      (footprint "eagle-import:R_2010")
      (libsource (lib "eagle-import") (part "R_RES_2010"))
    )
    (comp (ref "R8_4")
      (value "0")
      (footprint "eagle-import:R_0603")
      (libsource (lib "eagle-import") (part "R_RES_0603"))
    )
    (comp (ref "R9_4")
      (value "0")
      (footprint "eagle-import:R_0603")
      (libsource (lib "eagle-import") (part "R_RES_0603"))
    )
    (comp (ref "R18")
      (value "120")
      (footprint "eagle-import:1206")
      (libsource (lib "eagle-import") (part "RESISTOR1206"))
    )
    (comp (ref "R19")
      (value "120")
      (footprint "eagle-import:1206")
      (libsource (lib "eagle-import") (part "RESISTOR1206"))
    )
    (comp (ref "R20")
      (value "120")
      (footprint "eagle-import:1206")
      (libsource (lib "eagle-import") (part "RESISTOR1206"))
    )
    (comp (ref "S4")
      (value "J_MC32857")
      (footprint "eagle-import:J_TOGGLE")
      (libsource (lib "eagle-import") (part "J_MC32857"))
    )
    (comp (ref "X4")
      (value "HC49S")
      (footprint "eagle-import:HC-49")
      (libsource (lib "eagle-import") (part "X_HC49SCRYSTAL"))
    )
    (comp (ref "C1_2")
      (value ".1uF")
      (footprint "eagle-import:C_0805")
      (libsource (lib "eagle-import") (part "C_CAP_0805"))
    )
    (comp (ref "C2_2")
      (value "15pF")
      (footprint "eagle-import:C_0805")
      (libsource (lib "eagle-import") (part "C_CAP_0805"))
    )
    (comp (ref "C3_2")
      (value "15pF")
      (footprint "eagle-import:C_0805")
      (libsource (lib "eagle-import") (part "C_CAP_0805"))
    )
    (comp (ref "C4_2")
      (value ".1uF")
      (footprint "eagle-import:C_0805")
      (libsource (lib "eagle-import") (part "C_CAP_0805"))
    )
    (comp (ref "C5_2")
      (value ".1uF")
      (footprint "eagle-import:C_0805")
      (libsource (lib "eagle-import") (part "C_CAP_0805"))
    )
    (comp (ref "C6_2")
      (value "0.22uF")
      (footprint "eagle-import:C_0805")
      (libsource (lib "eagle-import") (part "C_CAP_0805"))
    )
    (comp (ref "C7_2")
      (value ".1uF")
      (footprint "eagle-import:C_0805")
      (libsource (lib "eagle-import") (part "C_CAP_0805"))
    )
    (comp (ref "C8_2")
      (value ".1uF")
      (footprint "eagle-import:C_0805")
      (libsource (lib "eagle-import") (part "C_CAP_0805"))
    )
    (comp (ref "C9_2")
      (value "C_CAP_0805")
      (footprint "eagle-import:C_0805")
      (libsource (lib "eagle-import") (part "C_CAP_0805"))
    )
    (comp (ref "C10_2")
      (value "1uF")
      (footprint "eagle-import:C_0805")
      (libsource (lib "eagle-import") (part "C_CAP_0805"))
    )
    (comp (ref "C11_2")
      (value ".22uF")
      (footprint "eagle-import:C_0805")
      (libsource (lib "eagle-import") (part "C_CAP_0805"))
    )
    (comp (ref "C12_2")
      (value ".22uF")
      (footprint "eagle-import:C_0805")
      (libsource (lib "eagle-import") (part "C_CAP_0805"))
    )
    (comp (ref "E2")
      (value "J_MTA5P_100")
      (footprint "eagle-import:J_MTA100_5P")
      (libsource (lib "eagle-import") (part "J_MTA5P_100"))
    )
    (comp (ref "H2")
      (value "A3959")
      (footprint "eagle-import:DIP24")
      (libsource (lib "eagle-import") (part "Q_A3959"))
    )
    (comp (ref "JP5")
      (value "M025MM")
      (footprint "eagle-import:SCREWTERMINAL-5MM-2")
      (libsource (lib "eagle-import") (part "M025MM"))
    )
    (comp (ref "LED4")
      (value "LED1206")
      (footprint "eagle-import:LED-1206")
      (libsource (lib "eagle-import") (part "LED1206"))
    )
    (comp (ref "LED5")
      (value "LED1206")
      (footprint "eagle-import:LED-1206")
      (libsource (lib "eagle-import") (part "LED1206"))
    )
    (comp (ref "LED6")
      (value "LED1206")
      (footprint "eagle-import:LED-1206")
      (libsource (lib "eagle-import") (part "LED1206"))
    )
    (comp (ref "P2")
      (value "ATMEGA328P")
      (footprint "eagle-import:DIP28")
      (libsource (lib "eagle-import") (part "Q_ATMEGA328P"))
    )
    (comp (ref "R1_2")
      (value "200")
      (footprint "eagle-import:R_0805")
      (libsource (lib "eagle-import") (part "R_RES_0805"))
    )
    (comp (ref "R4_2")
      (value "51k")
      (footprint "eagle-import:R_0805")
      (libsource (lib "eagle-import") (part "R_RES_0805"))
    )
    (comp (ref "R5_2")
      (value "1k")
      (footprint "eagle-import:R_0805")
      (libsource (lib "eagle-import") (part "R_RES_0805"))
    )
    (comp (ref "R6_2")
      (value "10k")
      (footprint "eagle-import:R_0805")
      (libsource (lib "eagle-import") (part "R_RES_0805"))
    )
    (comp (ref "R7_2")
      (value "R_RES_2010")
      (footprint "eagle-import:R_2010")
      (libsource (lib "eagle-import") (part "R_RES_2010"))
    )
    (comp (ref "R8_2")
      (value "0")
      (footprint "eagle-import:R_0603")
      (libsource (lib "eagle-import") (part "R_RES_0603"))
    )
    (comp (ref "R9_2")
      (value "0")
      (footprint "eagle-import:R_0603")
      (libsource (lib "eagle-import") (part "R_RES_0603"))
    )
    (comp (ref "R12")
      (value "120")
      (footprint "eagle-import:1206")
      (libsource (lib "eagle-import") (part "RESISTOR1206"))
    )
    (comp (ref "R13")
      (value "120")
      (footprint "eagle-import:1206")
      (libsource (lib "eagle-import") (part "RESISTOR1206"))
    )
    (comp (ref "R14")
      (value "120")
      (footprint "eagle-import:1206")
      (libsource (lib "eagle-import") (part "RESISTOR1206"))
    )
    (comp (ref "S2")
      (value "J_MC32857")
      (footprint "eagle-import:J_TOGGLE")
      (libsource (lib "eagle-import") (part "J_MC32857"))
    )
    (comp (ref "X2")
      (value "HC49S")
      (footprint "eagle-import:HC-49")
      (libsource (lib "eagle-import") (part "X_HC49SCRYSTAL"))
    )
  )
  (nets
    (net (code "1") (name "B1") (class "Default")
      (node (ref "JP9") (pin "2") (pinfunction "2_2") (pintype "passive"))
      (node (ref "MP") (pin "4") (pinfunction "PD2_4") (pintype "bidirectional"))
      (node (ref "R28") (pin "2") (pinfunction "2_2") (pintype "passive"))
    )
    (net (code "2") (name "B2") (class "Default")
      (node (ref "JP10") (pin "2") (pinfunction "2_2") (pintype "passive"))
      (node (ref "MP") (pin "5") (pinfunction "PD3_5") (pintype "bidirectional"))
      (node (ref "R29") (pin "2") (pinfunction "2_2") (pintype "passive"))
    )
    (net (code "3") (name "B3") (class "Default")
      (node (ref "JP11") (pin "2") (pinfunction "2_2") (pintype "passive"))
      (node (ref "MP") (pin "6") (pinfunction "PD4_6") (pintype "bidirectional"))
      (node (ref "R30") (pin "2") (pinfunction "2_2") (pintype "passive"))
    )
    (net (code "4") (name "B4") (class "Default")
      (node (ref "JP12") (pin "2") (pinfunction "2_2") (pintype "passive"))
      (node (ref "MP") (pin "13") (pinfunction "PD7_13") (pintype "bidirectional"))
      (node (ref "R31") (pin "2") (pinfunction "2_2") (pintype "passive"))
    )
    (net (code "5") (name "B5") (class "Default")
      (node (ref "JP13") (pin "2") (pinfunction "2_2") (pintype "passive"))
      (node (ref "MP") (pin "14") (pinfunction "PB0_14") (pintype "bidirectional"))
      (node (ref "R32") (pin "2") (pinfunction "2_2") (pintype "passive"))
    )
    (net (code "6") (name "BLANK1") (class "Default")
      (node (ref "H1") (pin "12") (pinfunction "BLANK_12") (pintype "bidirectional"))
      (node (ref "P1") (pin "17") (pinfunction "PB3_17") (pintype "bidirectional"))
    )
    (net (code "7") (name "BLANK2") (class "Default")
      (node (ref "H2") (pin "12") (pinfunction "BLANK_12") (pintype "bidirectional"))
      (node (ref "P2") (pin "17") (pinfunction "PB3_17") (pintype "bidirectional"))
    )
    (net (code "8") (name "BLANK3") (class "Default")
      (node (ref "H3") (pin "12") (pinfunction "BLANK_12") (pintype "bidirectional"))
      (node (ref "P3") (pin "17") (pinfunction "PB3_17") (pintype "bidirectional"))
    )
    (net (code "9") (name "BLANK4") (class "Default")
      (node (ref "H4") (pin "12") (pinfunction "BLANK_12") (pintype "bidirectional"))
      (node (ref "P4") (pin "17") (pinfunction "PB3_17") (pintype "bidirectional"))
    )
    (net (code "10") (name "BLANK5") (class "Default")
      (node (ref "H5") (pin "12") (pinfunction "BLANK_12") (pintype "bidirectional"))
      (node (ref "P5") (pin "17") (pinfunction "PB3_17") (pintype "bidirectional"))
    )
    (net (code "11") (name "D+") (class "Default")
      (node (ref "O6") (pin "3") (pinfunction "3_3") (pintype "passive"))
      (node (ref "R10") (pin "P$2") (pinfunction "2_P$2") (pintype "passive"))
      (node (ref "U$26") (pin "6") (pinfunction "A_6") (pintype "bidirectional"))
    )
    (net (code "12") (name "D-") (class "Default")
      (node (ref "O6") (pin "4") (pinfunction "4_4") (pintype "passive"))
      (node (ref "R10") (pin "P$1") (pinfunction "1_P$1") (pintype "passive"))
      (node (ref "U$26") (pin "7") (pinfunction "B_7") (pintype "bidirectional"))
    )
    (net (code "13") (name "D1") (class "Default")
      (node (ref "P1") (pin "3") (pinfunction "PD1_3") (pintype "bidirectional"))
    )
    (net (code "14") (name "D2") (class "Default")
      (node (ref "P2") (pin "3") (pinfunction "PD1_3") (pintype "bidirectional"))
    )
    (net (code "15") (name "D3") (class "Default")
      (node (ref "P3") (pin "3") (pinfunction "PD1_3") (pintype "bidirectional"))
    )
    (net (code "16") (name "D4") (class "Default")
      (node (ref "P4") (pin "3") (pinfunction "PD1_3") (pintype "bidirectional"))
    )
    (net (code "17") (name "D5") (class "Default")
      (node (ref "P5") (pin "3") (pinfunction "PD1_3") (pintype "bidirectional"))
    )
    (net (code "18") (name "D7") (class "Default")
      (node (ref "P6") (pin "3") (pinfunction "PD1_3") (pintype "bidirectional"))
    )
    (net (code "19") (name "DIR6") (class "Default")
      (node (ref "P6") (pin "6") (pinfunction "PD4_6") (pintype "bidirectional"))
      (node (ref "U$26") (pin "2") (pinfunction "RE_2") (pintype "bidirectional"))
      (node (ref "U$26") (pin "3") (pinfunction "DE_3") (pintype "bidirectional"))
    )
    (net (code "20") (name "DM") (class "Default")
      (node (ref "MD") (pin "2") (pinfunction "2_2") (pintype "passive"))
      (node (ref "MP") (pin "3") (pinfunction "PD1_3") (pintype "bidirectional"))
      (node (ref "Q3") (pin "3") (pinfunction "D_3") (pintype "bidirectional"))
    )
    (net (code "21") (name "EN1") (class "Default")
      (node (ref "H1") (pin "10") (pinfunction "EN_10") (pintype "bidirectional"))
      (node (ref "P1") (pin "19") (pinfunction "PB5_19") (pintype "bidirectional"))
    )
    (net (code "22") (name "EN2") (class "Default")
      (node (ref "H2") (pin "10") (pinfunction "EN_10") (pintype "bidirectional"))
      (node (ref "P2") (pin "19") (pinfunction "PB5_19") (pintype "bidirectional"))
    )
    (net (code "23") (name "EN3") (class "Default")
      (node (ref "H3") (pin "10") (pinfunction "EN_10") (pintype "bidirectional"))
      (node (ref "P3") (pin "19") (pinfunction "PB5_19") (pintype "bidirectional"))
    )
    (net (code "24") (name "EN4") (class "Default")
      (node (ref "H4") (pin "10") (pinfunction "EN_10") (pintype "bidirectional"))
      (node (ref "P4") (pin "19") (pinfunction "PB5_19") (pintype "bidirectional"))
    )
    (net (code "25") (name "EN5") (class "Default")
      (node (ref "H5") (pin "10") (pinfunction "EN_10") (pintype "bidirectional"))
      (node (ref "P5") (pin "19") (pinfunction "PB5_19") (pintype "bidirectional"))
    )
    (net (code "26") (name "EXTMODE1") (class "Default")
      (node (ref "H1") (pin "15") (pinfunction "EXTMODE_15") (pintype "bidirectional"))
      (node (ref "P1") (pin "16") (pinfunction "PB2_16") (pintype "bidirectional"))
    )
    (net (code "27") (name "EXTMODE2") (class "Default")
      (node (ref "H2") (pin "15") (pinfunction "EXTMODE_15") (pintype "bidirectional"))
      (node (ref "P2") (pin "16") (pinfunction "PB2_16") (pintype "bidirectional"))
    )
    (net (code "28") (name "EXTMODE3") (class "Default")
      (node (ref "H3") (pin "15") (pinfunction "EXTMODE_15") (pintype "bidirectional"))
      (node (ref "P3") (pin "16") (pinfunction "PB2_16") (pintype "bidirectional"))
    )
    (net (code "29") (name "EXTMODE4") (class "Default")
      (node (ref "H4") (pin "15") (pinfunction "EXTMODE_15") (pintype "bidirectional"))
      (node (ref "P4") (pin "16") (pinfunction "PB2_16") (pintype "bidirectional"))
    )
    (net (code "30") (name "EXTMODE5") (class "Default")
      (node (ref "H5") (pin "15") (pinfunction "EXTMODE_15") (pintype "bidirectional"))
      (node (ref "P5") (pin "16") (pinfunction "PB2_16") (pintype "bidirectional"))
    )
    (net (code "31") (name "GND") (class "Default")
      (node (ref "C10") (pin "2") (pinfunction "2_2") (pintype "passive"))
      (node (ref "C10_1") (pin "1") (pinfunction "1_1") (pintype "passive"))
      (node (ref "C10_2") (pin "1") (pinfunction "1_1") (pintype "passive"))
      (node (ref "C10_3") (pin "1") (pinfunction "1_1") (pintype "passive"))
      (node (ref "C10_4") (pin "1") (pinfunction "1_1") (pintype "passive"))
      (node (ref "C10_5") (pin "1") (pinfunction "1_1") (pintype "passive"))
      (node (ref "C11_1") (pin "2") (pinfunction "2_2") (pintype "passive"))
      (node (ref "C11_2") (pin "2") (pinfunction "2_2") (pintype "passive"))
      (node (ref "C11_3") (pin "2") (pinfunction "2_2") (pintype "passive"))
      (node (ref "C11_4") (pin "2") (pinfunction "2_2") (pintype "passive"))
      (node (ref "C11_5") (pin "2") (pinfunction "2_2") (pintype "passive"))
      (node (ref "C12_1") (pin "1") (pinfunction "1_1") (pintype "passive"))
      (node (ref "C12_2") (pin "1") (pinfunction "1_1") (pintype "passive"))
      (node (ref "C12_3") (pin "1") (pinfunction "1_1") (pintype "passive"))
      (node (ref "C12_4") (pin "1") (pinfunction "1_1") (pintype "passive"))
      (node (ref "C12_5") (pin "1") (pinfunction "1_1") (pintype "passive"))
      (node (ref "C1_1") (pin "1") (pinfunction "1_1") (pintype "passive"))
      (node (ref "C1_2") (pin "1") (pinfunction "1_1") (pintype "passive"))
      (node (ref "C1_3") (pin "1") (pinfunction "1_1") (pintype "passive"))
      (node (ref "C1_4") (pin "1") (pinfunction "1_1") (pintype "passive"))
      (node (ref "C1_5") (pin "1") (pinfunction "1_1") (pintype "passive"))
      (node (ref "C1_6") (pin "1") (pinfunction "1_1") (pintype "passive"))
      (node (ref "C1_M") (pin "1") (pinfunction "1_1") (pintype "passive"))
      (node (ref "C2_1") (pin "1") (pinfunction "1_1") (pintype "passive"))
      (node (ref "C2_2") (pin "1") (pinfunction "1_1") (pintype "passive"))
      (node (ref "C2_3") (pin "1") (pinfunction "1_1") (pintype "passive"))
      (node (ref "C2_4") (pin "1") (pinfunction "1_1") (pintype "passive"))
      (node (ref "C2_5") (pin "1") (pinfunction "1_1") (pintype "passive"))
      (node (ref "C2_6") (pin "1") (pinfunction "1_1") (pintype "passive"))
      (node (ref "C2_M") (pin "1") (pinfunction "1_1") (pintype "passive"))
      (node (ref "C3_1") (pin "1") (pinfunction "1_1") (pintype "passive"))
      (node (ref "C3_2") (pin "1") (pinfunction "1_1") (pintype "passive"))
      (node (ref "C3_3") (pin "1") (pinfunction "1_1") (pintype "passive"))
      (node (ref "C3_4") (pin "1") (pinfunction "1_1") (pintype "passive"))
      (node (ref "C3_5") (pin "1") (pinfunction "1_1") (pintype "passive"))
      (node (ref "C3_6") (pin "1") (pinfunction "1_1") (pintype "passive"))
      (node (ref "C3_M") (pin "1") (pinfunction "1_1") (pintype "passive"))
      (node (ref "C4_1") (pin "2") (pinfunction "2_2") (pintype "passive"))
      (node (ref "C4_2") (pin "2") (pinfunction "2_2") (pintype "passive"))
      (node (ref "C4_3") (pin "2") (pinfunction "2_2") (pintype "passive"))
      (node (ref "C4_4") (pin "2") (pinfunction "2_2") (pintype "passive"))
      (node (ref "C4_5") (pin "2") (pinfunction "2_2") (pintype "passive"))
      (node (ref "C4_6") (pin "2") (pinfunction "2_2") (pintype "passive"))
      (node (ref "C4_M") (pin "2") (pinfunction "2_2") (pintype "passive"))
      (node (ref "C5_1") (pin "2") (pinfunction "2_2") (pintype "passive"))
      (node (ref "C5_2") (pin "2") (pinfunction "2_2") (pintype "passive"))
      (node (ref "C5_3") (pin "2") (pinfunction "2_2") (pintype "passive"))
      (node (ref "C5_4") (pin "2") (pinfunction "2_2") (pintype "passive"))
      (node (ref "C5_5") (pin "2") (pinfunction "2_2") (pintype "passive"))
      (node (ref "C5_6") (pin "2") (pinfunction "2_2") (pintype "passive"))
      (node (ref "C5_M") (pin "2") (pinfunction "2_2") (pintype "passive"))
      (node (ref "C7_1") (pin "2") (pinfunction "2_2") (pintype "passive"))
      (node (ref "C7_2") (pin "2") (pinfunction "2_2") (pintype "passive"))
      (node (ref "C7_3") (pin "2") (pinfunction "2_2") (pintype "passive"))
      (node (ref "C7_4") (pin "2") (pinfunction "2_2") (pintype "passive"))
      (node (ref "C7_5") (pin "2") (pinfunction "2_2") (pintype "passive"))
      (node (ref "C8_1") (pin "2") (pinfunction "2_2") (pintype "passive"))
      (node (ref "C8_2") (pin "2") (pinfunction "2_2") (pintype "passive"))
      (node (ref "C8_3") (pin "2") (pinfunction "2_2") (pintype "passive"))
      (node (ref "C8_4") (pin "2") (pinfunction "2_2") (pintype "passive"))
      (node (ref "C8_5") (pin "2") (pinfunction "2_2") (pintype "passive"))
      (node (ref "C9_1") (pin "2") (pinfunction "2_2") (pintype "passive"))
      (node (ref "C9_2") (pin "2") (pinfunction "2_2") (pintype "passive"))
      (node (ref "C9_3") (pin "2") (pinfunction "2_2") (pintype "passive"))
      (node (ref "C9_4") (pin "2") (pinfunction "2_2") (pintype "passive"))
      (node (ref "C9_5") (pin "2") (pinfunction "2_2") (pintype "passive"))
      (node (ref "CV3") (pin "2") (pinfunction "2_2") (pintype "passive"))
      (node (ref "CV4") (pin "2") (pinfunction "2_2") (pintype "passive"))
      (node (ref "E1") (pin "5") (pinfunction "5_5") (pintype "passive"))
      (node (ref "E2") (pin "5") (pinfunction "5_5") (pintype "passive"))
      (node (ref "E3") (pin "5") (pinfunction "5_5") (pintype "passive"))
      (node (ref "E4") (pin "5") (pinfunction "5_5") (pintype "passive"))
      (node (ref "E5") (pin "5") (pinfunction "5_5") (pintype "passive"))
      (node (ref "H1") (pin "18") (pinfunction "GND4_18") (pintype "bidirectional"))
      (node (ref "H1") (pin "19") (pinfunction "GND5_19") (pintype "bidirectional"))
      (node (ref "H1") (pin "5") (pinfunction "GND_5") (pintype "bidirectional"))
      (node (ref "H1") (pin "6") (pinfunction "GND1_6") (pintype "bidirectional"))
      (node (ref "H1") (pin "7") (pinfunction "GND2_7") (pintype "bidirectional"))
      (node (ref "H1") (pin "8") (pinfunction "GND3_8") (pintype "bidirectional"))
      (node (ref "H2") (pin "18") (pinfunction "GND4_18") (pintype "bidirectional"))
      (node (ref "H2") (pin "19") (pinfunction "GND5_19") (pintype "bidirectional"))
      (node (ref "H2") (pin "5") (pinfunction "GND_5") (pintype "bidirectional"))
      (node (ref "H2") (pin "6") (pinfunction "GND1_6") (pintype "bidirectional"))
      (node (ref "H2") (pin "7") (pinfunction "GND2_7") (pintype "bidirectional"))
      (node (ref "H2") (pin "8") (pinfunction "GND3_8") (pintype "bidirectional"))
      (node (ref "H3") (pin "18") (pinfunction "GND4_18") (pintype "bidirectional"))
      (node (ref "H3") (pin "19") (pinfunction "GND5_19") (pintype "bidirectional"))
      (node (ref "H3") (pin "5") (pinfunction "GND_5") (pintype "bidirectional"))
      (node (ref "H3") (pin "6") (pinfunction "GND1_6") (pintype "bidirectional"))
      (node (ref "H3") (pin "7") (pinfunction "GND2_7") (pintype "bidirectional"))
      (node (ref "H3") (pin "8") (pinfunction "GND3_8") (pintype "bidirectional"))
      (node (ref "H4") (pin "18") (pinfunction "GND4_18") (pintype "bidirectional"))
      (node (ref "H4") (pin "19") (pinfunction "GND5_19") (pintype "bidirectional"))
      (node (ref "H4") (pin "5") (pinfunction "GND_5") (pintype "bidirectional"))
      (node (ref "H4") (pin "6") (pinfunction "GND1_6") (pintype "bidirectional"))
      (node (ref "H4") (pin "7") (pinfunction "GND2_7") (pintype "bidirectional"))
      (node (ref "H4") (pin "8") (pinfunction "GND3_8") (pintype "bidirectional"))
      (node (ref "H5") (pin "18") (pinfunction "GND4_18") (pintype "bidirectional"))
      (node (ref "H5") (pin "19") (pinfunction "GND5_19") (pintype "bidirectional"))
      (node (ref "H5") (pin "5") (pinfunction "GND_5") (pintype "bidirectional"))
      (node (ref "H5") (pin "6") (pinfunction "GND1_6") (pintype "bidirectional"))
      (node (ref "H5") (pin "7") (pinfunction "GND2_7") (pintype "bidirectional"))
      (node (ref "H5") (pin "8") (pinfunction "GND3_8") (pintype "bidirectional"))
      (node (ref "J6") (pin "P$1") (pinfunction "1_P$1") (pintype "bidirectional"))
      (node (ref "JP1") (pin "2") (pinfunction "2_2") (pintype "passive"))
      (node (ref "JP14") (pin "1") (pinfunction "1_1") (pintype "passive"))
      (node (ref "JP15") (pin "1") (pinfunction "1_1") (pintype "passive"))
      (node (ref "LED1") (pin "C") (pinfunction "C_C") (pintype "passive"))
      (node (ref "LED10") (pin "C") (pinfunction "C_C") (pintype "passive"))
      (node (ref "LED11") (pin "C") (pinfunction "C_C") (pintype "passive"))
      (node (ref "LED12") (pin "C") (pinfunction "C_C") (pintype "passive"))
      (node (ref "LED13") (pin "C") (pinfunction "C_C") (pintype "passive"))
      (node (ref "LED14") (pin "C") (pinfunction "C_C") (pintype "passive"))
      (node (ref "LED15") (pin "C") (pinfunction "C_C") (pintype "passive"))
      (node (ref "LED16") (pin "C") (pinfunction "C_C") (pintype "passive"))
      (node (ref "LED17") (pin "C") (pinfunction "C_C") (pintype "passive"))
      (node (ref "LED18") (pin "C") (pinfunction "C_C") (pintype "passive"))
      (node (ref "LED2") (pin "C") (pinfunction "C_C") (pintype "passive"))
      (node (ref "LED21") (pin "C") (pinfunction "C_C") (pintype "passive"))
      (node (ref "LED3") (pin "C") (pinfunction "C_C") (pintype "passive"))
      (node (ref "LED4") (pin "C") (pinfunction "C_C") (pintype "passive"))
      (node (ref "LED5") (pin "C") (pinfunction "C_C") (pintype "passive"))
      (node (ref "LED6") (pin "C") (pinfunction "C_C") (pintype "passive"))
      (node (ref "LED7") (pin "C") (pinfunction "C_C") (pintype "passive"))
      (node (ref "LED8") (pin "C") (pinfunction "C_C") (pintype "passive"))
      (node (ref "LED9") (pin "C") (pinfunction "C_C") (pintype "passive"))
      (node (ref "MD") (pin "1") (pinfunction "1_1") (pintype "passive"))
      (node (ref "MP") (pin "22") (pinfunction "GND1_22") (pintype "bidirectional"))
      (node (ref "MP") (pin "8") (pinfunction "GND_8") (pintype "bidirectional"))
      (node (ref "MS") (pin "P$1") (pinfunction "1_P$1") (pintype "bidirectional"))
      (node (ref "MS1") (pin "P$1") (pinfunction "1_P$1") (pintype "bidirectional"))
      (node (ref "O6") (pin "1") (pinfunction "1_1") (pintype "passive"))
      (node (ref "P1") (pin "22") (pinfunction "GND1_22") (pintype "bidirectional"))
      (node (ref "P1") (pin "8") (pinfunction "GND_8") (pintype "bidirectional"))
      (node (ref "P2") (pin "22") (pinfunction "GND1_22") (pintype "bidirectional"))
      (node (ref "P2") (pin "8") (pinfunction "GND_8") (pintype "bidirectional"))
      (node (ref "P3") (pin "22") (pinfunction "GND1_22") (pintype "bidirectional"))
      (node (ref "P3") (pin "8") (pinfunction "GND_8") (pintype "bidirectional"))
      (node (ref "P4") (pin "22") (pinfunction "GND1_22") (pintype "bidirectional"))
      (node (ref "P4") (pin "8") (pinfunction "GND_8") (pintype "bidirectional"))
      (node (ref "P5") (pin "22") (pinfunction "GND1_22") (pintype "bidirectional"))
      (node (ref "P5") (pin "8") (pinfunction "GND_8") (pintype "bidirectional"))
      (node (ref "P6") (pin "22") (pinfunction "GND1_22") (pintype "bidirectional"))
      (node (ref "P6") (pin "8") (pinfunction "GND_8") (pintype "bidirectional"))
      (node (ref "Q1") (pin "3") (pinfunction "S_3") (pintype "passive"))
      (node (ref "Q2") (pin "3") (pinfunction "S_3") (pintype "passive"))
      (node (ref "Q3") (pin "4") (pinfunction "GND_4") (pintype "bidirectional"))
      (node (ref "Q4") (pin "3") (pinfunction "S_3") (pintype "passive"))
      (node (ref "Q5") (pin "2") (pinfunction "GND_2") (pintype "bidirectional"))
      (node (ref "R28") (pin "1") (pinfunction "1_1") (pintype "passive"))
      (node (ref "R29") (pin "1") (pinfunction "1_1") (pintype "passive"))
      (node (ref "R3") (pin "P$1") (pinfunction "1_P$1") (pintype "passive"))
      (node (ref "R30") (pin "1") (pinfunction "1_1") (pintype "passive"))
      (node (ref "R31") (pin "1") (pinfunction "1_1") (pintype "passive"))
      (node (ref "R32") (pin "1") (pinfunction "1_1") (pintype "passive"))
      (node (ref "R6") (pin "P$1") (pinfunction "1_P$1") (pintype "passive"))
      (node (ref "R6_1") (pin "2") (pinfunction "2_2") (pintype "passive"))
      (node (ref "R6_2") (pin "2") (pinfunction "2_2") (pintype "passive"))
      (node (ref "R6_3") (pin "2") (pinfunction "2_2") (pintype "passive"))
      (node (ref "R6_4") (pin "2") (pinfunction "2_2") (pintype "passive"))
      (node (ref "R6_5") (pin "2") (pinfunction "2_2") (pintype "passive"))
      (node (ref "R7") (pin "P$1") (pinfunction "1_P$1") (pintype "passive"))
      (node (ref "R7_1") (pin "2") (pinfunction "2_2") (pintype "passive"))
      (node (ref "R7_2") (pin "2") (pinfunction "2_2") (pintype "passive"))
      (node (ref "R7_3") (pin "2") (pinfunction "2_2") (pintype "passive"))
      (node (ref "R7_4") (pin "2") (pinfunction "2_2") (pintype "passive"))
      (node (ref "R7_5") (pin "2") (pinfunction "2_2") (pintype "passive"))
      (node (ref "S1") (pin "P$1") (pinfunction "1_P$1") (pintype "bidirectional"))
      (node (ref "S2") (pin "P$1") (pinfunction "1_P$1") (pintype "bidirectional"))
      (node (ref "S3") (pin "P$1") (pinfunction "1_P$1") (pintype "bidirectional"))
      (node (ref "S4") (pin "P$1") (pinfunction "1_P$1") (pintype "bidirectional"))
      (node (ref "S5") (pin "P$1") (pinfunction "1_P$1") (pintype "bidirectional"))
      (node (ref "SJ1") (pin "1") (pinfunction "1_1") (pintype "passive"))
      (node (ref "U$26") (pin "5") (pinfunction "GND_5") (pintype "bidirectional"))
    )
    (net (code "32") (name "INTERRUPT1_1") (class "Default")
      (node (ref "E1") (pin "2") (pinfunction "2_2") (pintype "passive"))
      (node (ref "P1") (pin "5") (pinfunction "PD3_5") (pintype "bidirectional"))
      (node (ref "R9_1") (pin "1") (pinfunction "1_1") (pintype "passive"))
    )
    (net (code "33") (name "INTERRUPT1_2") (class "Default")
      (node (ref "E2") (pin "2") (pinfunction "2_2") (pintype "passive"))
      (node (ref "P2") (pin "5") (pinfunction "PD3_5") (pintype "bidirectional"))
      (node (ref "R9_2") (pin "1") (pinfunction "1_1") (pintype "passive"))
    )
    (net (code "34") (name "INTERRUPT1_3") (class "Default")
      (node (ref "E3") (pin "2") (pinfunction "2_2") (pintype "passive"))
      (node (ref "P3") (pin "5") (pinfunction "PD3_5") (pintype "bidirectional"))
      (node (ref "R9_3") (pin "1") (pinfunction "1_1") (pintype "passive"))
    )
    (net (code "35") (name "INTERRUPT1_4") (class "Default")
      (node (ref "E4") (pin "2") (pinfunction "2_2") (pintype "passive"))
      (node (ref "P4") (pin "5") (pinfunction "PD3_5") (pintype "bidirectional"))
      (node (ref "R9_4") (pin "1") (pinfunction "1_1") (pintype "passive"))
    )
    (net (code "36") (name "INTERRUPT1_5") (class "Default")
      (node (ref "E5") (pin "2") (pinfunction "2_2") (pintype "passive"))
      (node (ref "P5") (pin "5") (pinfunction "PD3_5") (pintype "bidirectional"))
      (node (ref "R9_5") (pin "1") (pinfunction "1_1") (pintype "passive"))
    )
    (net (code "37") (name "INTERRUPT2_1") (class "Default")
      (node (ref "E1") (pin "1") (pinfunction "1_1") (pintype "passive"))
      (node (ref "P1") (pin "4") (pinfunction "PD2_4") (pintype "bidirectional"))
    )
    (net (code "38") (name "INTERRUPT2_2") (class "Default")
      (node (ref "E2") (pin "1") (pinfunction "1_1") (pintype "passive"))
      (node (ref "P2") (pin "4") (pinfunction "PD2_4") (pintype "bidirectional"))
    )
    (net (code "39") (name "INTERRUPT2_3") (class "Default")
      (node (ref "E3") (pin "1") (pinfunction "1_1") (pintype "passive"))
      (node (ref "P3") (pin "4") (pinfunction "PD2_4") (pintype "bidirectional"))
    )
    (net (code "40") (name "INTERRUPT2_4") (class "Default")
      (node (ref "E4") (pin "1") (pinfunction "1_1") (pintype "passive"))
      (node (ref "P4") (pin "4") (pinfunction "PD2_4") (pintype "bidirectional"))
    )
    (net (code "41") (name "INTERRUPT2_5") (class "Default")
      (node (ref "E5") (pin "1") (pinfunction "1_1") (pintype "passive"))
      (node (ref "P5") (pin "4") (pinfunction "PD2_4") (pintype "bidirectional"))
    )
    (net (code "42") (name "ISENSE1") (class "Default")
      (node (ref "C9_1") (pin "1") (pinfunction "1_1") (pintype "passive"))
      (node (ref "H1") (pin "17") (pinfunction "SENSE_17") (pintype "bidirectional"))
      (node (ref "P1") (pin "26") (pinfunction "PC3_26") (pintype "bidirectional"))
      (node (ref "R7_1") (pin "1") (pinfunction "1_1") (pintype "passive"))
    )
    (net (code "43") (name "ISENSE2") (class "Default")
      (node (ref "C9_2") (pin "1") (pinfunction "1_1") (pintype "passive"))
      (node (ref "H2") (pin "17") (pinfunction "SENSE_17") (pintype "bidirectional"))
      (node (ref "P2") (pin "26") (pinfunction "PC3_26") (pintype "bidirectional"))
      (node (ref "R7_2") (pin "1") (pinfunction "1_1") (pintype "passive"))
    )
    (net (code "44") (name "ISENSE3") (class "Default")
      (node (ref "C9_3") (pin "1") (pinfunction "1_1") (pintype "passive"))
      (node (ref "H3") (pin "17") (pinfunction "SENSE_17") (pintype "bidirectional"))
      (node (ref "P3") (pin "26") (pinfunction "PC3_26") (pintype "bidirectional"))
      (node (ref "R7_3") (pin "1") (pinfunction "1_1") (pintype "passive"))
    )
    (net (code "45") (name "ISENSE4") (class "Default")
      (node (ref "C9_4") (pin "1") (pinfunction "1_1") (pintype "passive"))
      (node (ref "H4") (pin "17") (pinfunction "SENSE_17") (pintype "bidirectional"))
      (node (ref "P4") (pin "26") (pinfunction "PC3_26") (pintype "bidirectional"))
      (node (ref "R7_4") (pin "1") (pinfunction "1_1") (pintype "passive"))
    )
    (net (code "46") (name "ISENSE5") (class "Default")
      (node (ref "C9_5") (pin "1") (pinfunction "1_1") (pintype "passive"))
      (node (ref "H5") (pin "17") (pinfunction "SENSE_17") (pintype "bidirectional"))
      (node (ref "P5") (pin "26") (pinfunction "PC3_26") (pintype "bidirectional"))
      (node (ref "R7_5") (pin "1") (pinfunction "1_1") (pintype "passive"))
    )
    (net (code "47") (name "LED1_1") (class "Default")
      (node (ref "P1") (pin "12") (pinfunction "PD6_12") (pintype "bidirectional"))
      (node (ref "R8") (pin "2") (pinfunction "2_2") (pintype "passive"))
    )
    (net (code "48") (name "LED1_2") (class "Default")
      (node (ref "P2") (pin "12") (pinfunction "PD6_12") (pintype "bidirectional"))
      (node (ref "R12") (pin "2") (pinfunction "2_2") (pintype "passive"))
    )
    (net (code "49") (name "LED1_3") (class "Default")
      (node (ref "P3") (pin "12") (pinfunction "PD6_12") (pintype "bidirectional"))
      (node (ref "R15") (pin "2") (pinfunction "2_2") (pintype "passive"))
    )
    (net (code "50") (name "LED1_4") (class "Default")
      (node (ref "P4") (pin "12") (pinfunction "PD6_12") (pintype "bidirectional"))
      (node (ref "R18") (pin "2") (pinfunction "2_2") (pintype "passive"))
    )
    (net (code "51") (name "LED1_5") (class "Default")
      (node (ref "P5") (pin "12") (pinfunction "PD6_12") (pintype "bidirectional"))
      (node (ref "R21") (pin "2") (pinfunction "2_2") (pintype "passive"))
    )
    (net (code "52") (name "LED1_6") (class "Default")
      (node (ref "P6") (pin "12") (pinfunction "PD6_12") (pintype "bidirectional"))
      (node (ref "R24") (pin "2") (pinfunction "2_2") (pintype "passive"))
    )
    (net (code "53") (name "LED2_1") (class "Default")
      (node (ref "P1") (pin "13") (pinfunction "PD7_13") (pintype "bidirectional"))
      (node (ref "R9") (pin "2") (pinfunction "2_2") (pintype "passive"))
    )
    (net (code "54") (name "LED2_2") (class "Default")
      (node (ref "P2") (pin "13") (pinfunction "PD7_13") (pintype "bidirectional"))
      (node (ref "R13") (pin "2") (pinfunction "2_2") (pintype "passive"))
    )
    (net (code "55") (name "LED2_3") (class "Default")
      (node (ref "P3") (pin "13") (pinfunction "PD7_13") (pintype "bidirectional"))
      (node (ref "R16") (pin "2") (pinfunction "2_2") (pintype "passive"))
    )
    (net (code "56") (name "LED2_4") (class "Default")
      (node (ref "P4") (pin "13") (pinfunction "PD7_13") (pintype "bidirectional"))
      (node (ref "R19") (pin "2") (pinfunction "2_2") (pintype "passive"))
    )
    (net (code "57") (name "LED2_5") (class "Default")
      (node (ref "P5") (pin "13") (pinfunction "PD7_13") (pintype "bidirectional"))
      (node (ref "R22") (pin "2") (pinfunction "2_2") (pintype "passive"))
    )
    (net (code "58") (name "LED2_6") (class "Default")
      (node (ref "P6") (pin "13") (pinfunction "PD7_13") (pintype "bidirectional"))
      (node (ref "R25") (pin "2") (pinfunction "2_2") (pintype "passive"))
    )
    (net (code "59") (name "N$15") (class "Default")
      (node (ref "P1") (pin "1") (pinfunction "PC6_1") (pintype "bidirectional"))
      (node (ref "R11") (pin "2") (pinfunction "2_2") (pintype "passive"))
      (node (ref "R1_1") (pin "1") (pinfunction "1_1") (pintype "passive"))
      (node (ref "S1") (pin "P$2") (pinfunction "2_P$2") (pintype "bidirectional"))
    )
    (net (code "60") (name "N$30") (class "Default")
      (node (ref "P2") (pin "1") (pinfunction "PC6_1") (pintype "bidirectional"))
      (node (ref "R14") (pin "2") (pinfunction "2_2") (pintype "passive"))
      (node (ref "R1_2") (pin "1") (pinfunction "1_1") (pintype "passive"))
      (node (ref "S2") (pin "P$2") (pinfunction "2_P$2") (pintype "bidirectional"))
    )
    (net (code "61") (name "N$43") (class "Default")
      (node (ref "P3") (pin "1") (pinfunction "PC6_1") (pintype "bidirectional"))
      (node (ref "R17") (pin "2") (pinfunction "2_2") (pintype "passive"))
      (node (ref "R1_3") (pin "1") (pinfunction "1_1") (pintype "passive"))
      (node (ref "S3") (pin "P$2") (pinfunction "2_P$2") (pintype "bidirectional"))
    )
    (net (code "62") (name "N$56") (class "Default")
      (node (ref "P4") (pin "1") (pinfunction "PC6_1") (pintype "bidirectional"))
      (node (ref "R1_4") (pin "1") (pinfunction "1_1") (pintype "passive"))
      (node (ref "R20") (pin "2") (pinfunction "2_2") (pintype "passive"))
      (node (ref "S4") (pin "P$2") (pinfunction "2_P$2") (pintype "bidirectional"))
    )
    (net (code "63") (name "N$69") (class "Default")
      (node (ref "P5") (pin "1") (pinfunction "PC6_1") (pintype "bidirectional"))
      (node (ref "R1_5") (pin "1") (pinfunction "1_1") (pintype "passive"))
      (node (ref "R23") (pin "2") (pinfunction "2_2") (pintype "passive"))
      (node (ref "S5") (pin "P$2") (pinfunction "2_P$2") (pintype "bidirectional"))
    )
    (net (code "64") (name "N$88") (class "Default")
      (node (ref "MP") (pin "1") (pinfunction "PC6_1") (pintype "bidirectional"))
      (node (ref "MS") (pin "P$2") (pinfunction "2_P$2") (pintype "bidirectional"))
      (node (ref "R1_M") (pin "1") (pinfunction "1_1") (pintype "passive"))
      (node (ref "R27") (pin "2") (pinfunction "2_2") (pintype "passive"))
    )
    (net (code "65") (name "Net-(E1-Pad3)") (class "Default")
      (node (ref "E1") (pin "3") (pinfunction "3_3") (pintype "passive"))
      (node (ref "R8_1") (pin "1") (pinfunction "1_1") (pintype "passive"))
    )
    (net (code "66") (name "Net-(E2-Pad3)") (class "Default")
      (node (ref "E2") (pin "3") (pinfunction "3_3") (pintype "passive"))
      (node (ref "R8_2") (pin "1") (pinfunction "1_1") (pintype "passive"))
    )
    (net (code "67") (name "Net-(E3-Pad3)") (class "Default")
      (node (ref "E3") (pin "3") (pinfunction "3_3") (pintype "passive"))
      (node (ref "R8_3") (pin "1") (pinfunction "1_1") (pintype "passive"))
    )
    (net (code "68") (name "Net-(E4-Pad3)") (class "Default")
      (node (ref "E4") (pin "3") (pinfunction "3_3") (pintype "passive"))
      (node (ref "R8_4") (pin "1") (pinfunction "1_1") (pintype "passive"))
    )
    (net (code "69") (name "Net-(E5-Pad3)") (class "Default")
      (node (ref "E5") (pin "3") (pinfunction "3_3") (pintype "passive"))
      (node (ref "R8_5") (pin "1") (pinfunction "1_1") (pintype "passive"))
    )
    (net (code "70") (name "Net-(H1-CP)") (class "Default")
      (node (ref "C12_1") (pin "2") (pinfunction "2_2") (pintype "passive"))
      (node (ref "H1") (pin "24") (pinfunction "CP_24") (pintype "bidirectional"))
    )
    (net (code "71") (name "Net-(H1-CP1)") (class "Default")
      (node (ref "C6_1") (pin "2") (pinfunction "2_2") (pintype "passive"))
      (node (ref "H1") (pin "2") (pinfunction "CP1_2") (pintype "bidirectional"))
    )
    (net (code "72") (name "Net-(H1-CP2)") (class "Default")
      (node (ref "C6_1") (pin "1") (pinfunction "1_1") (pintype "passive"))
      (node (ref "H1") (pin "1") (pinfunction "CP2_1") (pintype "bidirectional"))
    )
    (net (code "73") (name "Net-(H1-REF)") (class "Default")
      (node (ref "C8_1") (pin "1") (pinfunction "1_1") (pintype "passive"))
      (node (ref "H1") (pin "14") (pinfunction "REF_14") (pintype "bidirectional"))
      (node (ref "R5_1") (pin "1") (pinfunction "1_1") (pintype "passive"))
      (node (ref "R6_1") (pin "1") (pinfunction "1_1") (pintype "passive"))
    )
    (net (code "74") (name "Net-(H1-ROSC)") (class "Default")
      (node (ref "H1") (pin "4") (pinfunction "ROSC_4") (pintype "bidirectional"))
      (node (ref "R4_1") (pin "2") (pinfunction "2_2") (pintype "passive"))
    )
    (net (code "75") (name "Net-(H1-VREG)") (class "Default")
      (node (ref "C11_1") (pin "1") (pinfunction "1_1") (pintype "passive"))
      (node (ref "H1") (pin "23") (pinfunction "VREG_23") (pintype "bidirectional"))
    )
    (net (code "76") (name "Net-(H2-CP)") (class "Default")
      (node (ref "C12_2") (pin "2") (pinfunction "2_2") (pintype "passive"))
      (node (ref "H2") (pin "24") (pinfunction "CP_24") (pintype "bidirectional"))
    )
    (net (code "77") (name "Net-(H2-CP1)") (class "Default")
      (node (ref "C6_2") (pin "2") (pinfunction "2_2") (pintype "passive"))
      (node (ref "H2") (pin "2") (pinfunction "CP1_2") (pintype "bidirectional"))
    )
    (net (code "78") (name "Net-(H2-CP2)") (class "Default")
      (node (ref "C6_2") (pin "1") (pinfunction "1_1") (pintype "passive"))
      (node (ref "H2") (pin "1") (pinfunction "CP2_1") (pintype "bidirectional"))
    )
    (net (code "79") (name "Net-(H2-REF)") (class "Default")
      (node (ref "C8_2") (pin "1") (pinfunction "1_1") (pintype "passive"))
      (node (ref "H2") (pin "14") (pinfunction "REF_14") (pintype "bidirectional"))
      (node (ref "R5_2") (pin "1") (pinfunction "1_1") (pintype "passive"))
      (node (ref "R6_2") (pin "1") (pinfunction "1_1") (pintype "passive"))
    )
    (net (code "80") (name "Net-(H2-ROSC)") (class "Default")
      (node (ref "H2") (pin "4") (pinfunction "ROSC_4") (pintype "bidirectional"))
      (node (ref "R4_2") (pin "2") (pinfunction "2_2") (pintype "passive"))
    )
    (net (code "81") (name "Net-(H2-VREG)") (class "Default")
      (node (ref "C11_2") (pin "1") (pinfunction "1_1") (pintype "passive"))
      (node (ref "H2") (pin "23") (pinfunction "VREG_23") (pintype "bidirectional"))
    )
    (net (code "82") (name "Net-(H3-CP)") (class "Default")
      (node (ref "C12_3") (pin "2") (pinfunction "2_2") (pintype "passive"))
      (node (ref "H3") (pin "24") (pinfunction "CP_24") (pintype "bidirectional"))
    )
    (net (code "83") (name "Net-(H3-CP1)") (class "Default")
      (node (ref "C6_3") (pin "2") (pinfunction "2_2") (pintype "passive"))
      (node (ref "H3") (pin "2") (pinfunction "CP1_2") (pintype "bidirectional"))
    )
    (net (code "84") (name "Net-(H3-CP2)") (class "Default")
      (node (ref "C6_3") (pin "1") (pinfunction "1_1") (pintype "passive"))
      (node (ref "H3") (pin "1") (pinfunction "CP2_1") (pintype "bidirectional"))
    )
    (net (code "85") (name "Net-(H3-REF)") (class "Default")
      (node (ref "C8_3") (pin "1") (pinfunction "1_1") (pintype "passive"))
      (node (ref "H3") (pin "14") (pinfunction "REF_14") (pintype "bidirectional"))
      (node (ref "R5_3") (pin "1") (pinfunction "1_1") (pintype "passive"))
      (node (ref "R6_3") (pin "1") (pinfunction "1_1") (pintype "passive"))
    )
    (net (code "86") (name "Net-(H3-ROSC)") (class "Default")
      (node (ref "H3") (pin "4") (pinfunction "ROSC_4") (pintype "bidirectional"))
      (node (ref "R4_3") (pin "2") (pinfunction "2_2") (pintype "passive"))
    )
    (net (code "87") (name "Net-(H3-VREG)") (class "Default")
      (node (ref "C11_3") (pin "1") (pinfunction "1_1") (pintype "passive"))
      (node (ref "H3") (pin "23") (pinfunction "VREG_23") (pintype "bidirectional"))
    )
    (net (code "88") (name "Net-(H4-CP)") (class "Default")
      (node (ref "C12_4") (pin "2") (pinfunction "2_2") (pintype "passive"))
      (node (ref "H4") (pin "24") (pinfunction "CP_24") (pintype "bidirectional"))
    )
    (net (code "89") (name "Net-(H4-CP1)") (class "Default")
      (node (ref "C6_4") (pin "2") (pinfunction "2_2") (pintype "passive"))
      (node (ref "H4") (pin "2") (pinfunction "CP1_2") (pintype "bidirectional"))
    )
    (net (code "90") (name "Net-(H4-CP2)") (class "Default")
      (node (ref "C6_4") (pin "1") (pinfunction "1_1") (pintype "passive"))
      (node (ref "H4") (pin "1") (pinfunction "CP2_1") (pintype "bidirectional"))
    )
    (net (code "91") (name "Net-(H4-REF)") (class "Default")
      (node (ref "C8_4") (pin "1") (pinfunction "1_1") (pintype "passive"))
      (node (ref "H4") (pin "14") (pinfunction "REF_14") (pintype "bidirectional"))
      (node (ref "R5_4") (pin "1") (pinfunction "1_1") (pintype "passive"))
      (node (ref "R6_4") (pin "1") (pinfunction "1_1") (pintype "passive"))
    )
    (net (code "92") (name "Net-(H4-ROSC)") (class "Default")
      (node (ref "H4") (pin "4") (pinfunction "ROSC_4") (pintype "bidirectional"))
      (node (ref "R4_4") (pin "2") (pinfunction "2_2") (pintype "passive"))
    )
    (net (code "93") (name "Net-(H4-VREG)") (class "Default")
      (node (ref "C11_4") (pin "1") (pinfunction "1_1") (pintype "passive"))
      (node (ref "H4") (pin "23") (pinfunction "VREG_23") (pintype "bidirectional"))
    )
    (net (code "94") (name "Net-(H5-CP)") (class "Default")
      (node (ref "C12_5") (pin "2") (pinfunction "2_2") (pintype "passive"))
      (node (ref "H5") (pin "24") (pinfunction "CP_24") (pintype "bidirectional"))
    )
    (net (code "95") (name "Net-(H5-CP1)") (class "Default")
      (node (ref "C6_5") (pin "2") (pinfunction "2_2") (pintype "passive"))
      (node (ref "H5") (pin "2") (pinfunction "CP1_2") (pintype "bidirectional"))
    )
    (net (code "96") (name "Net-(H5-CP2)") (class "Default")
      (node (ref "C6_5") (pin "1") (pinfunction "1_1") (pintype "passive"))
      (node (ref "H5") (pin "1") (pinfunction "CP2_1") (pintype "bidirectional"))
    )
    (net (code "97") (name "Net-(H5-REF)") (class "Default")
      (node (ref "C8_5") (pin "1") (pinfunction "1_1") (pintype "passive"))
      (node (ref "H5") (pin "14") (pinfunction "REF_14") (pintype "bidirectional"))
      (node (ref "R5_5") (pin "1") (pinfunction "1_1") (pintype "passive"))
      (node (ref "R6_5") (pin "1") (pinfunction "1_1") (pintype "passive"))
    )
    (net (code "98") (name "Net-(H5-ROSC)") (class "Default")
      (node (ref "H5") (pin "4") (pinfunction "ROSC_4") (pintype "bidirectional"))
      (node (ref "R4_5") (pin "2") (pinfunction "2_2") (pintype "passive"))
    )
    (net (code "99") (name "Net-(H5-VREG)") (class "Default")
      (node (ref "C11_5") (pin "1") (pinfunction "1_1") (pintype "passive"))
      (node (ref "H5") (pin "23") (pinfunction "VREG_23") (pintype "bidirectional"))
    )
    (net (code "100") (name "Net-(LED1-PadA)") (class "Default")
      (node (ref "LED1") (pin "A") (pinfunction "A_A") (pintype "passive"))
      (node (ref "R11") (pin "1") (pinfunction "1_1") (pintype "passive"))
    )
    (net (code "101") (name "Net-(LED2-PadA)") (class "Default")
      (node (ref "LED2") (pin "A") (pinfunction "A_A") (pintype "passive"))
      (node (ref "R9") (pin "1") (pinfunction "1_1") (pintype "passive"))
    )
    (net (code "102") (name "Net-(LED3-PadA)") (class "Default")
      (node (ref "LED3") (pin "A") (pinfunction "A_A") (pintype "passive"))
      (node (ref "R8") (pin "1") (pinfunction "1_1") (pintype "passive"))
    )
    (net (code "103") (name "Net-(LED4-PadA)") (class "Default")
      (node (ref "LED4") (pin "A") (pinfunction "A_A") (pintype "passive"))
      (node (ref "R14") (pin "1") (pinfunction "1_1") (pintype "passive"))
    )
    (net (code "104") (name "Net-(LED5-PadA)") (class "Default")
      (node (ref "LED5") (pin "A") (pinfunction "A_A") (pintype "passive"))
      (node (ref "R13") (pin "1") (pinfunction "1_1") (pintype "passive"))
    )
    (net (code "105") (name "Net-(LED6-PadA)") (class "Default")
      (node (ref "LED6") (pin "A") (pinfunction "A_A") (pintype "passive"))
      (node (ref "R12") (pin "1") (pinfunction "1_1") (pintype "passive"))
    )
    (net (code "106") (name "Net-(LED7-PadA)") (class "Default")
      (node (ref "LED7") (pin "A") (pinfunction "A_A") (pintype "passive"))
      (node (ref "R17") (pin "1") (pinfunction "1_1") (pintype "passive"))
    )
    (net (code "107") (name "Net-(LED8-PadA)") (class "Default")
      (node (ref "LED8") (pin "A") (pinfunction "A_A") (pintype "passive"))
      (node (ref "R16") (pin "1") (pinfunction "1_1") (pintype "passive"))
    )
    (net (code "108") (name "Net-(LED9-PadA)") (class "Default")
      (node (ref "LED9") (pin "A") (pinfunction "A_A") (pintype "passive"))
      (node (ref "R15") (pin "1") (pinfunction "1_1") (pintype "passive"))
    )
    (net (code "109") (name "Net-(LED10-PadA)") (class "Default")
      (node (ref "LED10") (pin "A") (pinfunction "A_A") (pintype "passive"))
      (node (ref "R20") (pin "1") (pinfunction "1_1") (pintype "passive"))
    )
    (net (code "110") (name "Net-(LED11-PadA)") (class "Default")
      (node (ref "LED11") (pin "A") (pinfunction "A_A") (pintype "passive"))
      (node (ref "R19") (pin "1") (pinfunction "1_1") (pintype "passive"))
    )
    (net (code "111") (name "Net-(LED12-PadA)") (class "Default")
      (node (ref "LED12") (pin "A") (pinfunction "A_A") (pintype "passive"))
      (node (ref "R18") (pin "1") (pinfunction "1_1") (pintype "passive"))
    )
    (net (code "112") (name "Net-(LED13-PadA)") (class "Default")
      (node (ref "LED13") (pin "A") (pinfunction "A_A") (pintype "passive"))
      (node (ref "R23") (pin "1") (pinfunction "1_1") (pintype "passive"))
    )
    (net (code "113") (name "Net-(LED14-PadA)") (class "Default")
      (node (ref "LED14") (pin "A") (pinfunction "A_A") (pintype "passive"))
      (node (ref "R22") (pin "1") (pinfunction "1_1") (pintype "passive"))
    )
    (net (code "114") (name "Net-(LED15-PadA)") (class "Default")
      (node (ref "LED15") (pin "A") (pinfunction "A_A") (pintype "passive"))
      (node (ref "R21") (pin "1") (pinfunction "1_1") (pintype "passive"))
    )
    (net (code "115") (name "Net-(LED16-PadA)") (class "Default")
      (node (ref "LED16") (pin "A") (pinfunction "A_A") (pintype "passive"))
      (node (ref "R26") (pin "1") (pinfunction "1_1") (pintype "passive"))
    )
    (net (code "116") (name "Net-(LED17-PadA)") (class "Default")
      (node (ref "LED17") (pin "A") (pinfunction "A_A") (pintype "passive"))
      (node (ref "R25") (pin "1") (pinfunction "1_1") (pintype "passive"))
    )
    (net (code "117") (name "Net-(LED18-PadA)") (class "Default")
      (node (ref "LED18") (pin "A") (pinfunction "A_A") (pintype "passive"))
      (node (ref "R24") (pin "1") (pinfunction "1_1") (pintype "passive"))
    )
    (net (code "118") (name "Net-(LED21-PadA)") (class "Default")
      (node (ref "LED21") (pin "A") (pinfunction "A_A") (pintype "passive"))
      (node (ref "R27") (pin "1") (pinfunction "1_1") (pintype "passive"))
    )
    (net (code "119") (name "Net-(MP-AREF)") (class "Default")
      (node (ref "C5_M") (pin "1") (pinfunction "1_1") (pintype "passive"))
      (node (ref "MP") (pin "21") (pinfunction "AREF_21") (pintype "bidirectional"))
    )
    (net (code "120") (name "Net-(MP-PC3)") (class "Default")
      (node (ref "MP") (pin "26") (pinfunction "PC3_26") (pintype "bidirectional"))
      (node (ref "MS1") (pin "P$2") (pinfunction "2_P$2") (pintype "bidirectional"))
      (node (ref "R1_M1") (pin "1") (pinfunction "1_1") (pintype "passive"))
    )
    (net (code "121") (name "Net-(MP-XTAL1)") (class "Default")
      (node (ref "C2_M") (pin "2") (pinfunction "2_2") (pintype "passive"))
      (node (ref "MP") (pin "9") (pinfunction "XTAL1_9") (pintype "bidirectional"))
      (node (ref "MX") (pin "P$2") (pinfunction "2_P$2") (pintype "passive"))
    )
    (net (code "122") (name "Net-(MP-XTAL2)") (class "Default")
      (node (ref "C3_M") (pin "2") (pinfunction "2_2") (pintype "passive"))
      (node (ref "MP") (pin "10") (pinfunction "XTAL2_10") (pintype "bidirectional"))
      (node (ref "MX") (pin "P$1") (pinfunction "1_P$1") (pintype "passive"))
    )
    (net (code "123") (name "Net-(P1-AREF)") (class "Default")
      (node (ref "C5_1") (pin "1") (pinfunction "1_1") (pintype "passive"))
      (node (ref "P1") (pin "21") (pinfunction "AREF_21") (pintype "bidirectional"))
    )
    (net (code "124") (name "Net-(P1-XTAL1)") (class "Default")
      (node (ref "C2_1") (pin "2") (pinfunction "2_2") (pintype "passive"))
      (node (ref "P1") (pin "9") (pinfunction "XTAL1_9") (pintype "bidirectional"))
      (node (ref "X1") (pin "P$2") (pinfunction "2_P$2") (pintype "passive"))
    )
    (net (code "125") (name "Net-(P1-XTAL2)") (class "Default")
      (node (ref "C3_1") (pin "2") (pinfunction "2_2") (pintype "passive"))
      (node (ref "P1") (pin "10") (pinfunction "XTAL2_10") (pintype "bidirectional"))
      (node (ref "X1") (pin "P$1") (pinfunction "1_P$1") (pintype "passive"))
    )
    (net (code "126") (name "Net-(P2-AREF)") (class "Default")
      (node (ref "C5_2") (pin "1") (pinfunction "1_1") (pintype "passive"))
      (node (ref "P2") (pin "21") (pinfunction "AREF_21") (pintype "bidirectional"))
    )
    (net (code "127") (name "Net-(P2-XTAL1)") (class "Default")
      (node (ref "C2_2") (pin "2") (pinfunction "2_2") (pintype "passive"))
      (node (ref "P2") (pin "9") (pinfunction "XTAL1_9") (pintype "bidirectional"))
      (node (ref "X2") (pin "P$2") (pinfunction "2_P$2") (pintype "passive"))
    )
    (net (code "128") (name "Net-(P2-XTAL2)") (class "Default")
      (node (ref "C3_2") (pin "2") (pinfunction "2_2") (pintype "passive"))
      (node (ref "P2") (pin "10") (pinfunction "XTAL2_10") (pintype "bidirectional"))
      (node (ref "X2") (pin "P$1") (pinfunction "1_P$1") (pintype "passive"))
    )
    (net (code "129") (name "Net-(P3-AREF)") (class "Default")
      (node (ref "C5_3") (pin "1") (pinfunction "1_1") (pintype "passive"))
      (node (ref "P3") (pin "21") (pinfunction "AREF_21") (pintype "bidirectional"))
    )
    (net (code "130") (name "Net-(P3-XTAL1)") (class "Default")
      (node (ref "C2_3") (pin "2") (pinfunction "2_2") (pintype "passive"))
      (node (ref "P3") (pin "9") (pinfunction "XTAL1_9") (pintype "bidirectional"))
      (node (ref "X3") (pin "P$2") (pinfunction "2_P$2") (pintype "passive"))
    )
    (net (code "131") (name "Net-(P3-XTAL2)") (class "Default")
      (node (ref "C3_3") (pin "2") (pinfunction "2_2") (pintype "passive"))
      (node (ref "P3") (pin "10") (pinfunction "XTAL2_10") (pintype "bidirectional"))
      (node (ref "X3") (pin "P$1") (pinfunction "1_P$1") (pintype "passive"))
    )
    (net (code "132") (name "Net-(P4-AREF)") (class "Default")
      (node (ref "C5_4") (pin "1") (pinfunction "1_1") (pintype "passive"))
      (node (ref "P4") (pin "21") (pinfunction "AREF_21") (pintype "bidirectional"))
    )
    (net (code "133") (name "Net-(P4-XTAL1)") (class "Default")
      (node (ref "C2_4") (pin "2") (pinfunction "2_2") (pintype "passive"))
      (node (ref "P4") (pin "9") (pinfunction "XTAL1_9") (pintype "bidirectional"))
      (node (ref "X4") (pin "P$2") (pinfunction "2_P$2") (pintype "passive"))
    )
    (net (code "134") (name "Net-(P4-XTAL2)") (class "Default")
      (node (ref "C3_4") (pin "2") (pinfunction "2_2") (pintype "passive"))
      (node (ref "P4") (pin "10") (pinfunction "XTAL2_10") (pintype "bidirectional"))
      (node (ref "X4") (pin "P$1") (pinfunction "1_P$1") (pintype "passive"))
    )
    (net (code "135") (name "Net-(P5-AREF)") (class "Default")
      (node (ref "C5_5") (pin "1") (pinfunction "1_1") (pintype "passive"))
      (node (ref "P5") (pin "21") (pinfunction "AREF_21") (pintype "bidirectional"))
    )
    (net (code "136") (name "Net-(P5-XTAL1)") (class "Default")
      (node (ref "C2_5") (pin "2") (pinfunction "2_2") (pintype "passive"))
      (node (ref "P5") (pin "9") (pinfunction "XTAL1_9") (pintype "bidirectional"))
      (node (ref "X5") (pin "P$2") (pinfunction "2_P$2") (pintype "passive"))
    )
    (net (code "137") (name "Net-(P5-XTAL2)") (class "Default")
      (node (ref "C3_5") (pin "2") (pinfunction "2_2") (pintype "passive"))
      (node (ref "P5") (pin "10") (pinfunction "XTAL2_10") (pintype "bidirectional"))
      (node (ref "X5") (pin "P$1") (pinfunction "1_P$1") (pintype "passive"))
    )
    (net (code "138") (name "Net-(P6-AREF)") (class "Default")
      (node (ref "C5_6") (pin "1") (pinfunction "1_1") (pintype "passive"))
      (node (ref "P6") (pin "21") (pinfunction "AREF_21") (pintype "bidirectional"))
    )
    (net (code "139") (name "Net-(P6-XTAL1)") (class "Default")
      (node (ref "C2_6") (pin "2") (pinfunction "2_2") (pintype "passive"))
      (node (ref "P6") (pin "9") (pinfunction "XTAL1_9") (pintype "bidirectional"))
      (node (ref "X6") (pin "P$2") (pinfunction "2_P$2") (pintype "passive"))
    )
    (net (code "140") (name "Net-(P6-XTAL2)") (class "Default")
      (node (ref "C3_6") (pin "2") (pinfunction "2_2") (pintype "passive"))
      (node (ref "P6") (pin "10") (pinfunction "XTAL2_10") (pintype "bidirectional"))
      (node (ref "X6") (pin "P$1") (pinfunction "1_P$1") (pintype "passive"))
    )
    (net (code "141") (name "Net-(Q3-A)") (class "Default")
      (node (ref "Q3") (pin "8") (pinfunction "A_8") (pintype "bidirectional"))
      (node (ref "R4") (pin "P$1") (pinfunction "1_P$1") (pintype "passive"))
      (node (ref "U$2") (pin "3") (pinfunction "3_3") (pintype "bidirectional"))
    )
    (net (code "142") (name "Net-(Q3-B)") (class "Default")
      (node (ref "Q3") (pin "7") (pinfunction "B_7") (pintype "bidirectional"))
      (node (ref "R4") (pin "P$2") (pinfunction "2_P$2") (pintype "passive"))
      (node (ref "U$2") (pin "6") (pinfunction "6_6") (pintype "bidirectional"))
    )
    (net (code "143") (name "Net-(Q3-Y)") (class "Default")
      (node (ref "Q3") (pin "5") (pinfunction "Y_5") (pintype "bidirectional"))
      (node (ref "R5") (pin "P$2") (pinfunction "2_P$2") (pintype "passive"))
      (node (ref "U$2") (pin "1") (pinfunction "1_1") (pintype "bidirectional"))
    )
    (net (code "144") (name "Net-(Q3-Z)") (class "Default")
      (node (ref "Q3") (pin "6") (pinfunction "Z_6") (pintype "bidirectional"))
      (node (ref "R5") (pin "P$1") (pinfunction "1_P$1") (pintype "passive"))
      (node (ref "U$2") (pin "2") (pinfunction "2_2") (pintype "bidirectional"))
    )
    (net (code "145") (name "Net-(SJ1-Pad2)") (class "Default")
      (node (ref "SJ1") (pin "2") (pinfunction "2_2") (pintype "passive"))
      (node (ref "U$2") (pin "7") (pinfunction "7_7") (pintype "bidirectional"))
      (node (ref "U$2") (pin "8") (pinfunction "8_8") (pintype "bidirectional"))
    )
    (net (code "146") (name "O1") (class "Default")
      (node (ref "JP7") (pin "2") (pinfunction "2_2") (pintype "passive"))
      (node (ref "JP8") (pin "2") (pinfunction "2_2") (pintype "passive"))
      (node (ref "Q1") (pin "2") (pinfunction "D_2") (pintype "passive"))
    )
    (net (code "147") (name "O2") (class "Default")
      (node (ref "JP7") (pin "3") (pinfunction "3_3") (pintype "passive"))
      (node (ref "JP8") (pin "3") (pinfunction "3_3") (pintype "passive"))
      (node (ref "Q2") (pin "2") (pinfunction "D_2") (pintype "passive"))
    )
    (net (code "148") (name "O3") (class "Default")
      (node (ref "JP7") (pin "4") (pinfunction "4_4") (pintype "passive"))
      (node (ref "JP8") (pin "4") (pinfunction "4_4") (pintype "passive"))
      (node (ref "Q4") (pin "2") (pinfunction "D_2") (pintype "passive"))
    )
    (net (code "149") (name "OUTA1") (class "Default")
      (node (ref "H1") (pin "16") (pinfunction "OUTA_16") (pintype "bidirectional"))
      (node (ref "JP6") (pin "2") (pinfunction "2_2") (pintype "passive"))
    )
    (net (code "150") (name "OUTA2") (class "Default")
      (node (ref "H2") (pin "16") (pinfunction "OUTA_16") (pintype "bidirectional"))
      (node (ref "JP5") (pin "2") (pinfunction "2_2") (pintype "passive"))
    )
    (net (code "151") (name "OUTA3") (class "Default")
      (node (ref "H3") (pin "16") (pinfunction "OUTA_16") (pintype "bidirectional"))
      (node (ref "JP4") (pin "2") (pinfunction "2_2") (pintype "passive"))
    )
    (net (code "152") (name "OUTA4") (class "Default")
      (node (ref "H4") (pin "16") (pinfunction "OUTA_16") (pintype "bidirectional"))
      (node (ref "JP3") (pin "2") (pinfunction "2_2") (pintype "passive"))
    )
    (net (code "153") (name "OUTA5") (class "Default")
      (node (ref "H5") (pin "16") (pinfunction "OUTA_16") (pintype "bidirectional"))
      (node (ref "JP2") (pin "2") (pinfunction "2_2") (pintype "passive"))
    )
    (net (code "154") (name "OUTB1") (class "Default")
      (node (ref "H1") (pin "21") (pinfunction "OUTB_21") (pintype "bidirectional"))
      (node (ref "JP6") (pin "1") (pinfunction "1_1") (pintype "passive"))
    )
    (net (code "155") (name "OUTB2") (class "Default")
      (node (ref "H2") (pin "21") (pinfunction "OUTB_21") (pintype "bidirectional"))
      (node (ref "JP5") (pin "1") (pinfunction "1_1") (pintype "passive"))
    )
    (net (code "156") (name "OUTB3") (class "Default")
      (node (ref "H3") (pin "21") (pinfunction "OUTB_21") (pintype "bidirectional"))
      (node (ref "JP4") (pin "1") (pinfunction "1_1") (pintype "passive"))
    )
    (net (code "157") (name "OUTB4") (class "Default")
      (node (ref "H4") (pin "21") (pinfunction "OUTB_21") (pintype "bidirectional"))
      (node (ref "JP3") (pin "1") (pinfunction "1_1") (pintype "passive"))
    )
    (net (code "158") (name "OUTB5") (class "Default")
      (node (ref "H5") (pin "21") (pinfunction "OUTB_21") (pintype "bidirectional"))
      (node (ref "JP2") (pin "1") (pinfunction "1_1") (pintype "passive"))
    )
    (net (code "159") (name "PFD1_1") (class "Default")
      (node (ref "H1") (pin "13") (pinfunction "PFD1_13") (pintype "bidirectional"))
      (node (ref "P1") (pin "14") (pinfunction "PB0_14") (pintype "bidirectional"))
    )
    (net (code "160") (name "PFD1_2") (class "Default")
      (node (ref "H2") (pin "13") (pinfunction "PFD1_13") (pintype "bidirectional"))
      (node (ref "P2") (pin "14") (pinfunction "PB0_14") (pintype "bidirectional"))
    )
    (net (code "161") (name "PFD1_3") (class "Default")
      (node (ref "H3") (pin "13") (pinfunction "PFD1_13") (pintype "bidirectional"))
      (node (ref "P3") (pin "14") (pinfunction "PB0_14") (pintype "bidirectional"))
    )
    (net (code "162") (name "PFD1_4") (class "Default")
      (node (ref "H4") (pin "13") (pinfunction "PFD1_13") (pintype "bidirectional"))
      (node (ref "P4") (pin "14") (pinfunction "PB0_14") (pintype "bidirectional"))
    )
    (net (code "163") (name "PFD1_5") (class "Default")
      (node (ref "H5") (pin "13") (pinfunction "PFD1_13") (pintype "bidirectional"))
      (node (ref "P5") (pin "14") (pinfunction "PB0_14") (pintype "bidirectional"))
    )
    (net (code "164") (name "PFD2_1") (class "Default")
      (node (ref "H1") (pin "11") (pinfunction "PFD2_11") (pintype "bidirectional"))
      (node (ref "P1") (pin "18") (pinfunction "PB4_18") (pintype "bidirectional"))
    )
    (net (code "165") (name "PFD2_2") (class "Default")
      (node (ref "H2") (pin "11") (pinfunction "PFD2_11") (pintype "bidirectional"))
      (node (ref "P2") (pin "18") (pinfunction "PB4_18") (pintype "bidirectional"))
    )
    (net (code "166") (name "PFD2_3") (class "Default")
      (node (ref "H3") (pin "11") (pinfunction "PFD2_11") (pintype "bidirectional"))
      (node (ref "P3") (pin "18") (pinfunction "PB4_18") (pintype "bidirectional"))
    )
    (net (code "167") (name "PFD2_4") (class "Default")
      (node (ref "H4") (pin "11") (pinfunction "PFD2_11") (pintype "bidirectional"))
      (node (ref "P4") (pin "18") (pinfunction "PB4_18") (pintype "bidirectional"))
    )
    (net (code "168") (name "PFD2_5") (class "Default")
      (node (ref "H5") (pin "11") (pinfunction "PFD2_11") (pintype "bidirectional"))
      (node (ref "P5") (pin "18") (pinfunction "PB4_18") (pintype "bidirectional"))
    )
    (net (code "169") (name "PHASE1") (class "Default")
      (node (ref "H1") (pin "3") (pinfunction "PHASE_3") (pintype "bidirectional"))
      (node (ref "P1") (pin "23") (pinfunction "PC0_23") (pintype "bidirectional"))
    )
    (net (code "170") (name "PHASE2") (class "Default")
      (node (ref "H2") (pin "3") (pinfunction "PHASE_3") (pintype "bidirectional"))
      (node (ref "P2") (pin "23") (pinfunction "PC0_23") (pintype "bidirectional"))
    )
    (net (code "171") (name "PHASE3") (class "Default")
      (node (ref "H3") (pin "3") (pinfunction "PHASE_3") (pintype "bidirectional"))
      (node (ref "P3") (pin "23") (pinfunction "PC0_23") (pintype "bidirectional"))
    )
    (net (code "172") (name "PHASE4") (class "Default")
      (node (ref "H4") (pin "3") (pinfunction "PHASE_3") (pintype "bidirectional"))
      (node (ref "P4") (pin "23") (pinfunction "PC0_23") (pintype "bidirectional"))
    )
    (net (code "173") (name "PHASE5") (class "Default")
      (node (ref "H5") (pin "3") (pinfunction "PHASE_3") (pintype "bidirectional"))
      (node (ref "P5") (pin "23") (pinfunction "PC0_23") (pintype "bidirectional"))
    )
    (net (code "174") (name "PULSE1") (class "Default")
      (node (ref "P1") (pin "11") (pinfunction "PD5_11") (pintype "bidirectional"))
      (node (ref "R8_1") (pin "2") (pinfunction "2_2") (pintype "passive"))
      (node (ref "R9_1") (pin "2") (pinfunction "2_2") (pintype "passive"))
    )
    (net (code "175") (name "PULSE2") (class "Default")
      (node (ref "P2") (pin "11") (pinfunction "PD5_11") (pintype "bidirectional"))
      (node (ref "R8_2") (pin "2") (pinfunction "2_2") (pintype "passive"))
      (node (ref "R9_2") (pin "2") (pinfunction "2_2") (pintype "passive"))
    )
    (net (code "176") (name "PULSE3") (class "Default")
      (node (ref "P3") (pin "11") (pinfunction "PD5_11") (pintype "bidirectional"))
      (node (ref "R8_3") (pin "2") (pinfunction "2_2") (pintype "passive"))
      (node (ref "R9_3") (pin "2") (pinfunction "2_2") (pintype "passive"))
    )
    (net (code "177") (name "PULSE4") (class "Default")
      (node (ref "P4") (pin "11") (pinfunction "PD5_11") (pintype "bidirectional"))
      (node (ref "R8_4") (pin "2") (pinfunction "2_2") (pintype "passive"))
      (node (ref "R9_4") (pin "2") (pinfunction "2_2") (pintype "passive"))
    )
    (net (code "178") (name "PULSE5") (class "Default")
      (node (ref "P5") (pin "11") (pinfunction "PD5_11") (pintype "bidirectional"))
      (node (ref "R8_5") (pin "2") (pinfunction "2_2") (pintype "passive"))
      (node (ref "R9_5") (pin "2") (pinfunction "2_2") (pintype "passive"))
    )
    (net (code "179") (name "PWM1") (class "Default")
      (node (ref "JP15") (pin "3") (pinfunction "3_3") (pintype "passive"))
      (node (ref "MP") (pin "11") (pinfunction "PD5_11") (pintype "bidirectional"))
    )
    (net (code "180") (name "PWM2") (class "Default")
      (node (ref "JP14") (pin "3") (pinfunction "3_3") (pintype "passive"))
      (node (ref "MP") (pin "12") (pinfunction "PD6_12") (pintype "bidirectional"))
    )
    (net (code "181") (name "R1") (class "Default")
      (node (ref "P1") (pin "2") (pinfunction "PD0_2") (pintype "bidirectional"))
    )
    (net (code "182") (name "R2") (class "Default")
      (node (ref "P2") (pin "2") (pinfunction "PD0_2") (pintype "bidirectional"))
    )
    (net (code "183") (name "R3") (class "Default")
      (node (ref "P3") (pin "2") (pinfunction "PD0_2") (pintype "bidirectional"))
    )
    (net (code "184") (name "R4") (class "Default")
      (node (ref "P4") (pin "2") (pinfunction "PD0_2") (pintype "bidirectional"))
    )
    (net (code "185") (name "R5") (class "Default")
      (node (ref "P5") (pin "2") (pinfunction "PD0_2") (pintype "bidirectional"))
    )
    (net (code "186") (name "R7") (class "Default")
      (node (ref "P6") (pin "2") (pinfunction "PD0_2") (pintype "bidirectional"))
    )
    (net (code "187") (name "REF1_1") (class "Default")
      (node (ref "P1") (pin "15") (pinfunction "PB1_15") (pintype "bidirectional"))
      (node (ref "R5_1") (pin "2") (pinfunction "2_2") (pintype "passive"))
    )
    (net (code "188") (name "REF1_2") (class "Default")
      (node (ref "P2") (pin "15") (pinfunction "PB1_15") (pintype "bidirectional"))
      (node (ref "R5_2") (pin "2") (pinfunction "2_2") (pintype "passive"))
    )
    (net (code "189") (name "REF1_3") (class "Default")
      (node (ref "P3") (pin "15") (pinfunction "PB1_15") (pintype "bidirectional"))
      (node (ref "R5_3") (pin "2") (pinfunction "2_2") (pintype "passive"))
    )
    (net (code "190") (name "REF1_4") (class "Default")
      (node (ref "P4") (pin "15") (pinfunction "PB1_15") (pintype "bidirectional"))
      (node (ref "R5_4") (pin "2") (pinfunction "2_2") (pintype "passive"))
    )
    (net (code "191") (name "REF1_5") (class "Default")
      (node (ref "P5") (pin "15") (pinfunction "PB1_15") (pintype "bidirectional"))
      (node (ref "R5_5") (pin "2") (pinfunction "2_2") (pintype "passive"))
    )
    (net (code "192") (name "RM") (class "Default")
      (node (ref "MD") (pin "3") (pinfunction "3_3") (pintype "passive"))
      (node (ref "MP") (pin "2") (pinfunction "PD0_2") (pintype "bidirectional"))
      (node (ref "Q3") (pin "2") (pinfunction "R_2") (pintype "bidirectional"))
    )
    (net (code "193") (name "S1") (class "Default")
      (node (ref "MP") (pin "15") (pinfunction "PB1_15") (pintype "bidirectional"))
      (node (ref "Q1") (pin "1") (pinfunction "G_1") (pintype "passive"))
      (node (ref "R3") (pin "P$2") (pinfunction "2_P$2") (pintype "passive"))
    )
    (net (code "194") (name "S2") (class "Default")
      (node (ref "MP") (pin "16") (pinfunction "PB2_16") (pintype "bidirectional"))
      (node (ref "Q2") (pin "1") (pinfunction "G_1") (pintype "passive"))
      (node (ref "R6") (pin "P$2") (pinfunction "2_P$2") (pintype "passive"))
    )
    (net (code "195") (name "S3") (class "Default")
      (node (ref "MP") (pin "17") (pinfunction "PB3_17") (pintype "bidirectional"))
      (node (ref "Q4") (pin "1") (pinfunction "G_1") (pintype "passive"))
      (node (ref "R7") (pin "P$2") (pinfunction "2_P$2") (pintype "passive"))
    )
    (net (code "196") (name "S6") (class "Default")
      (node (ref "J6") (pin "P$2") (pinfunction "2_P$2") (pintype "bidirectional"))
      (node (ref "P6") (pin "1") (pinfunction "PC6_1") (pintype "bidirectional"))
      (node (ref "R1_6") (pin "1") (pinfunction "1_1") (pintype "passive"))
      (node (ref "R26") (pin "2") (pinfunction "2_2") (pintype "passive"))
    )
    (net (code "197") (name "SCL") (class "Default")
      (node (ref "MP") (pin "28") (pinfunction "PC5_28") (pintype "bidirectional"))
      (node (ref "P1") (pin "28") (pinfunction "PC5_28") (pintype "bidirectional"))
      (node (ref "P2") (pin "28") (pinfunction "PC5_28") (pintype "bidirectional"))
      (node (ref "P3") (pin "28") (pinfunction "PC5_28") (pintype "bidirectional"))
      (node (ref "P4") (pin "28") (pinfunction "PC5_28") (pintype "bidirectional"))
      (node (ref "P5") (pin "28") (pinfunction "PC5_28") (pintype "bidirectional"))
      (node (ref "P6") (pin "28") (pinfunction "PC5_28") (pintype "bidirectional"))
      (node (ref "R1") (pin "P$2") (pinfunction "2_P$2") (pintype "passive"))
    )
    (net (code "198") (name "SD6") (class "Default")
      (node (ref "P6") (pin "5") (pinfunction "PD3_5") (pintype "bidirectional"))
      (node (ref "U$26") (pin "4") (pinfunction "DI_4") (pintype "bidirectional"))
    )
    (net (code "199") (name "SDA") (class "Default")
      (node (ref "MP") (pin "27") (pinfunction "PC4_27") (pintype "bidirectional"))
      (node (ref "P1") (pin "27") (pinfunction "PC4_27") (pintype "bidirectional"))
      (node (ref "P2") (pin "27") (pinfunction "PC4_27") (pintype "bidirectional"))
      (node (ref "P3") (pin "27") (pinfunction "PC4_27") (pintype "bidirectional"))
      (node (ref "P4") (pin "27") (pinfunction "PC4_27") (pintype "bidirectional"))
      (node (ref "P5") (pin "27") (pinfunction "PC4_27") (pintype "bidirectional"))
      (node (ref "P6") (pin "27") (pinfunction "PC4_27") (pintype "bidirectional"))
      (node (ref "R2") (pin "P$2") (pinfunction "2_P$2") (pintype "passive"))
    )
    (net (code "200") (name "SLEEP1_1") (class "Default")
      (node (ref "H1") (pin "22") (pinfunction "SLEEP_22") (pintype "bidirectional"))
      (node (ref "P1") (pin "24") (pinfunction "PC1_24") (pintype "bidirectional"))
    )
    (net (code "201") (name "SLEEP1_2") (class "Default")
      (node (ref "H2") (pin "22") (pinfunction "SLEEP_22") (pintype "bidirectional"))
      (node (ref "P2") (pin "24") (pinfunction "PC1_24") (pintype "bidirectional"))
    )
    (net (code "202") (name "SLEEP1_3") (class "Default")
      (node (ref "H3") (pin "22") (pinfunction "SLEEP_22") (pintype "bidirectional"))
      (node (ref "P3") (pin "24") (pinfunction "PC1_24") (pintype "bidirectional"))
    )
    (net (code "203") (name "SLEEP1_4") (class "Default")
      (node (ref "H4") (pin "22") (pinfunction "SLEEP_22") (pintype "bidirectional"))
      (node (ref "P4") (pin "24") (pinfunction "PC1_24") (pintype "bidirectional"))
    )
    (net (code "204") (name "SLEEP1_5") (class "Default")
      (node (ref "H5") (pin "22") (pinfunction "SLEEP_22") (pintype "bidirectional"))
      (node (ref "P5") (pin "24") (pinfunction "PC1_24") (pintype "bidirectional"))
    )
    (net (code "205") (name "SR6") (class "Default")
      (node (ref "P6") (pin "4") (pinfunction "PD2_4") (pintype "bidirectional"))
      (node (ref "U$26") (pin "1") (pinfunction "RO_1") (pintype "bidirectional"))
    )
    (net (code "206") (name "V5") (class "Default")
      (node (ref "C10") (pin "1") (pinfunction "1_1") (pintype "passive"))
      (node (ref "C1_1") (pin "2") (pinfunction "2_2") (pintype "passive"))
      (node (ref "C1_2") (pin "2") (pinfunction "2_2") (pintype "passive"))
      (node (ref "C1_3") (pin "2") (pinfunction "2_2") (pintype "passive"))
      (node (ref "C1_4") (pin "2") (pinfunction "2_2") (pintype "passive"))
      (node (ref "C1_5") (pin "2") (pinfunction "2_2") (pintype "passive"))
      (node (ref "C1_6") (pin "2") (pinfunction "2_2") (pintype "passive"))
      (node (ref "C1_M") (pin "2") (pinfunction "2_2") (pintype "passive"))
      (node (ref "C4_1") (pin "1") (pinfunction "1_1") (pintype "passive"))
      (node (ref "C4_2") (pin "1") (pinfunction "1_1") (pintype "passive"))
      (node (ref "C4_3") (pin "1") (pinfunction "1_1") (pintype "passive"))
      (node (ref "C4_4") (pin "1") (pinfunction "1_1") (pintype "passive"))
      (node (ref "C4_5") (pin "1") (pinfunction "1_1") (pintype "passive"))
      (node (ref "C4_6") (pin "1") (pinfunction "1_1") (pintype "passive"))
      (node (ref "C4_M") (pin "1") (pinfunction "1_1") (pintype "passive"))
      (node (ref "C7_1") (pin "1") (pinfunction "1_1") (pintype "passive"))
      (node (ref "C7_2") (pin "1") (pinfunction "1_1") (pintype "passive"))
      (node (ref "C7_3") (pin "1") (pinfunction "1_1") (pintype "passive"))
      (node (ref "C7_4") (pin "1") (pinfunction "1_1") (pintype "passive"))
      (node (ref "C7_5") (pin "1") (pinfunction "1_1") (pintype "passive"))
      (node (ref "CV4") (pin "1") (pinfunction "1_1") (pintype "passive"))
      (node (ref "E1") (pin "4") (pinfunction "4_4") (pintype "passive"))
      (node (ref "E2") (pin "4") (pinfunction "4_4") (pintype "passive"))
      (node (ref "E3") (pin "4") (pinfunction "4_4") (pintype "passive"))
      (node (ref "E4") (pin "4") (pinfunction "4_4") (pintype "passive"))
      (node (ref "E5") (pin "4") (pinfunction "4_4") (pintype "passive"))
      (node (ref "H1") (pin "9") (pinfunction "VDD_9") (pintype "bidirectional"))
      (node (ref "H2") (pin "9") (pinfunction "VDD_9") (pintype "bidirectional"))
      (node (ref "H3") (pin "9") (pinfunction "VDD_9") (pintype "bidirectional"))
      (node (ref "H4") (pin "9") (pinfunction "VDD_9") (pintype "bidirectional"))
      (node (ref "H5") (pin "9") (pinfunction "VDD_9") (pintype "bidirectional"))
      (node (ref "JP10") (pin "1") (pinfunction "1_1") (pintype "passive"))
      (node (ref "JP11") (pin "1") (pinfunction "1_1") (pintype "passive"))
      (node (ref "JP12") (pin "1") (pinfunction "1_1") (pintype "passive"))
      (node (ref "JP13") (pin "1") (pinfunction "1_1") (pintype "passive"))
      (node (ref "JP14") (pin "2") (pinfunction "2_2") (pintype "passive"))
      (node (ref "JP15") (pin "2") (pinfunction "2_2") (pintype "passive"))
      (node (ref "JP9") (pin "1") (pinfunction "1_1") (pintype "passive"))
      (node (ref "MP") (pin "20") (pinfunction "AVCC_20") (pintype "bidirectional"))
      (node (ref "MP") (pin "7") (pinfunction "VCC_7") (pintype "bidirectional"))
      (node (ref "P1") (pin "20") (pinfunction "AVCC_20") (pintype "bidirectional"))
      (node (ref "P1") (pin "7") (pinfunction "VCC_7") (pintype "bidirectional"))
      (node (ref "P2") (pin "20") (pinfunction "AVCC_20") (pintype "bidirectional"))
      (node (ref "P2") (pin "7") (pinfunction "VCC_7") (pintype "bidirectional"))
      (node (ref "P3") (pin "20") (pinfunction "AVCC_20") (pintype "bidirectional"))
      (node (ref "P3") (pin "7") (pinfunction "VCC_7") (pintype "bidirectional"))
      (node (ref "P4") (pin "20") (pinfunction "AVCC_20") (pintype "bidirectional"))
      (node (ref "P4") (pin "7") (pinfunction "VCC_7") (pintype "bidirectional"))
      (node (ref "P5") (pin "20") (pinfunction "AVCC_20") (pintype "bidirectional"))
      (node (ref "P5") (pin "7") (pinfunction "VCC_7") (pintype "bidirectional"))
      (node (ref "P6") (pin "20") (pinfunction "AVCC_20") (pintype "bidirectional"))
      (node (ref "P6") (pin "7") (pinfunction "VCC_7") (pintype "bidirectional"))
      (node (ref "Q3") (pin "1") (pinfunction "VCC_1") (pintype "bidirectional"))
      (node (ref "Q5") (pin "3") (pinfunction "VOUT_3") (pintype "bidirectional"))
      (node (ref "R1") (pin "P$1") (pinfunction "1_P$1") (pintype "passive"))
      (node (ref "R1_1") (pin "2") (pinfunction "2_2") (pintype "passive"))
      (node (ref "R1_2") (pin "2") (pinfunction "2_2") (pintype "passive"))
      (node (ref "R1_3") (pin "2") (pinfunction "2_2") (pintype "passive"))
      (node (ref "R1_4") (pin "2") (pinfunction "2_2") (pintype "passive"))
      (node (ref "R1_5") (pin "2") (pinfunction "2_2") (pintype "passive"))
      (node (ref "R1_6") (pin "2") (pinfunction "2_2") (pintype "passive"))
      (node (ref "R1_M") (pin "2") (pinfunction "2_2") (pintype "passive"))
      (node (ref "R1_M1") (pin "2") (pinfunction "2_2") (pintype "passive"))
      (node (ref "R2") (pin "P$1") (pinfunction "1_P$1") (pintype "passive"))
      (node (ref "R4_1") (pin "1") (pinfunction "1_1") (pintype "passive"))
      (node (ref "R4_2") (pin "1") (pinfunction "1_1") (pintype "passive"))
      (node (ref "R4_3") (pin "1") (pinfunction "1_1") (pintype "passive"))
      (node (ref "R4_4") (pin "1") (pinfunction "1_1") (pintype "passive"))
      (node (ref "R4_5") (pin "1") (pinfunction "1_1") (pintype "passive"))
      (node (ref "U$26") (pin "8") (pinfunction "VCC_8") (pintype "bidirectional"))
    )
    (net (code "207") (name "VIN") (class "Default")
      (node (ref "C10_1") (pin "2") (pinfunction "2_2") (pintype "passive"))
      (node (ref "C10_2") (pin "2") (pinfunction "2_2") (pintype "passive"))
      (node (ref "C10_3") (pin "2") (pinfunction "2_2") (pintype "passive"))
      (node (ref "C10_4") (pin "2") (pinfunction "2_2") (pintype "passive"))
      (node (ref "C10_5") (pin "2") (pinfunction "2_2") (pintype "passive"))
      (node (ref "CV3") (pin "1") (pinfunction "1_1") (pintype "passive"))
      (node (ref "H1") (pin "20") (pinfunction "VBB_20") (pintype "bidirectional"))
      (node (ref "H2") (pin "20") (pinfunction "VBB_20") (pintype "bidirectional"))
      (node (ref "H3") (pin "20") (pinfunction "VBB_20") (pintype "bidirectional"))
      (node (ref "H4") (pin "20") (pinfunction "VBB_20") (pintype "bidirectional"))
      (node (ref "H5") (pin "20") (pinfunction "VBB_20") (pintype "bidirectional"))
      (node (ref "JP1") (pin "1") (pinfunction "1_1") (pintype "passive"))
      (node (ref "JP7") (pin "1") (pinfunction "1_1") (pintype "passive"))
      (node (ref "JP8") (pin "1") (pinfunction "1_1") (pintype "passive"))
      (node (ref "O6") (pin "2") (pinfunction "2_2") (pintype "passive"))
      (node (ref "Q5") (pin "1") (pinfunction "VIN_1") (pintype "bidirectional"))
    )
    (net (code "208") (name "unconnected-(MP-PB4-Pad18)") (class "Default")
      (node (ref "MP") (pin "18") (pinfunction "PB4_18") (pintype "bidirectional"))
    )
    (net (code "209") (name "unconnected-(MP-PB5-Pad19)") (class "Default")
      (node (ref "MP") (pin "19") (pinfunction "PB5_19") (pintype "bidirectional"))
    )
    (net (code "210") (name "unconnected-(MP-PC0-Pad23)") (class "Default")
      (node (ref "MP") (pin "23") (pinfunction "PC0_23") (pintype "bidirectional"))
    )
    (net (code "211") (name "unconnected-(MP-PC1-Pad24)") (class "Default")
      (node (ref "MP") (pin "24") (pinfunction "PC1_24") (pintype "bidirectional"))
    )
    (net (code "212") (name "unconnected-(MP-PC2-Pad25)") (class "Default")
      (node (ref "MP") (pin "25") (pinfunction "PC2_25") (pintype "bidirectional"))
    )
    (net (code "213") (name "unconnected-(P1-PC2-Pad25)") (class "Default")
      (node (ref "P1") (pin "25") (pinfunction "PC2_25") (pintype "bidirectional"))
    )
    (net (code "214") (name "unconnected-(P1-PD4-Pad6)") (class "Default")
      (node (ref "P1") (pin "6") (pinfunction "PD4_6") (pintype "bidirectional"))
    )
    (net (code "215") (name "unconnected-(P2-PC2-Pad25)") (class "Default")
      (node (ref "P2") (pin "25") (pinfunction "PC2_25") (pintype "bidirectional"))
    )
    (net (code "216") (name "unconnected-(P2-PD4-Pad6)") (class "Default")
      (node (ref "P2") (pin "6") (pinfunction "PD4_6") (pintype "bidirectional"))
    )
    (net (code "217") (name "unconnected-(P3-PC2-Pad25)") (class "Default")
      (node (ref "P3") (pin "25") (pinfunction "PC2_25") (pintype "bidirectional"))
    )
    (net (code "218") (name "unconnected-(P3-PD4-Pad6)") (class "Default")
      (node (ref "P3") (pin "6") (pinfunction "PD4_6") (pintype "bidirectional"))
    )
    (net (code "219") (name "unconnected-(P4-PC2-Pad25)") (class "Default")
      (node (ref "P4") (pin "25") (pinfunction "PC2_25") (pintype "bidirectional"))
    )
    (net (code "220") (name "unconnected-(P4-PD4-Pad6)") (class "Default")
      (node (ref "P4") (pin "6") (pinfunction "PD4_6") (pintype "bidirectional"))
    )
    (net (code "221") (name "unconnected-(P5-PC2-Pad25)") (class "Default")
      (node (ref "P5") (pin "25") (pinfunction "PC2_25") (pintype "bidirectional"))
    )
    (net (code "222") (name "unconnected-(P5-PD4-Pad6)") (class "Default")
      (node (ref "P5") (pin "6") (pinfunction "PD4_6") (pintype "bidirectional"))
    )
    (net (code "223") (name "unconnected-(P6-PB0-Pad14)") (class "Default")
      (node (ref "P6") (pin "14") (pinfunction "PB0_14") (pintype "bidirectional"))
    )
    (net (code "224") (name "unconnected-(P6-PB1-Pad15)") (class "Default")
      (node (ref "P6") (pin "15") (pinfunction "PB1_15") (pintype "bidirectional"))
    )
    (net (code "225") (name "unconnected-(P6-PB2-Pad16)") (class "Default")
      (node (ref "P6") (pin "16") (pinfunction "PB2_16") (pintype "bidirectional"))
    )
    (net (code "226") (name "unconnected-(P6-PB3-Pad17)") (class "Default")
      (node (ref "P6") (pin "17") (pinfunction "PB3_17") (pintype "bidirectional"))
    )
    (net (code "227") (name "unconnected-(P6-PB4-Pad18)") (class "Default")
      (node (ref "P6") (pin "18") (pinfunction "PB4_18") (pintype "bidirectional"))
    )
    (net (code "228") (name "unconnected-(P6-PB5-Pad19)") (class "Default")
      (node (ref "P6") (pin "19") (pinfunction "PB5_19") (pintype "bidirectional"))
    )
    (net (code "229") (name "unconnected-(P6-PC0-Pad23)") (class "Default")
      (node (ref "P6") (pin "23") (pinfunction "PC0_23") (pintype "bidirectional"))
    )
    (net (code "230") (name "unconnected-(P6-PC1-Pad24)") (class "Default")
      (node (ref "P6") (pin "24") (pinfunction "PC1_24") (pintype "bidirectional"))
    )
    (net (code "231") (name "unconnected-(P6-PC2-Pad25)") (class "Default")
      (node (ref "P6") (pin "25") (pinfunction "PC2_25") (pintype "bidirectional"))
    )
    (net (code "232") (name "unconnected-(P6-PC3-Pad26)") (class "Default")
      (node (ref "P6") (pin "26") (pinfunction "PC3_26") (pintype "bidirectional"))
    )
    (net (code "233") (name "unconnected-(P6-PD5-Pad11)") (class "Default")
      (node (ref "P6") (pin "11") (pinfunction "PD5_11") (pintype "bidirectional"))
    )
    (net (code "234") (name "unconnected-(U$2-Pad4)") (class "Default")
      (node (ref "U$2") (pin "4") (pinfunction "4_4") (pintype "bidirectional"))
    )
    (net (code "235") (name "unconnected-(U$2-Pad5)") (class "Default")
      (node (ref "U$2") (pin "5") (pinfunction "5_5") (pintype "bidirectional"))
    )
  )
)
